# 612_jetracer_328_213.net
KiCad netlist of a schematic drawn in EAGLE
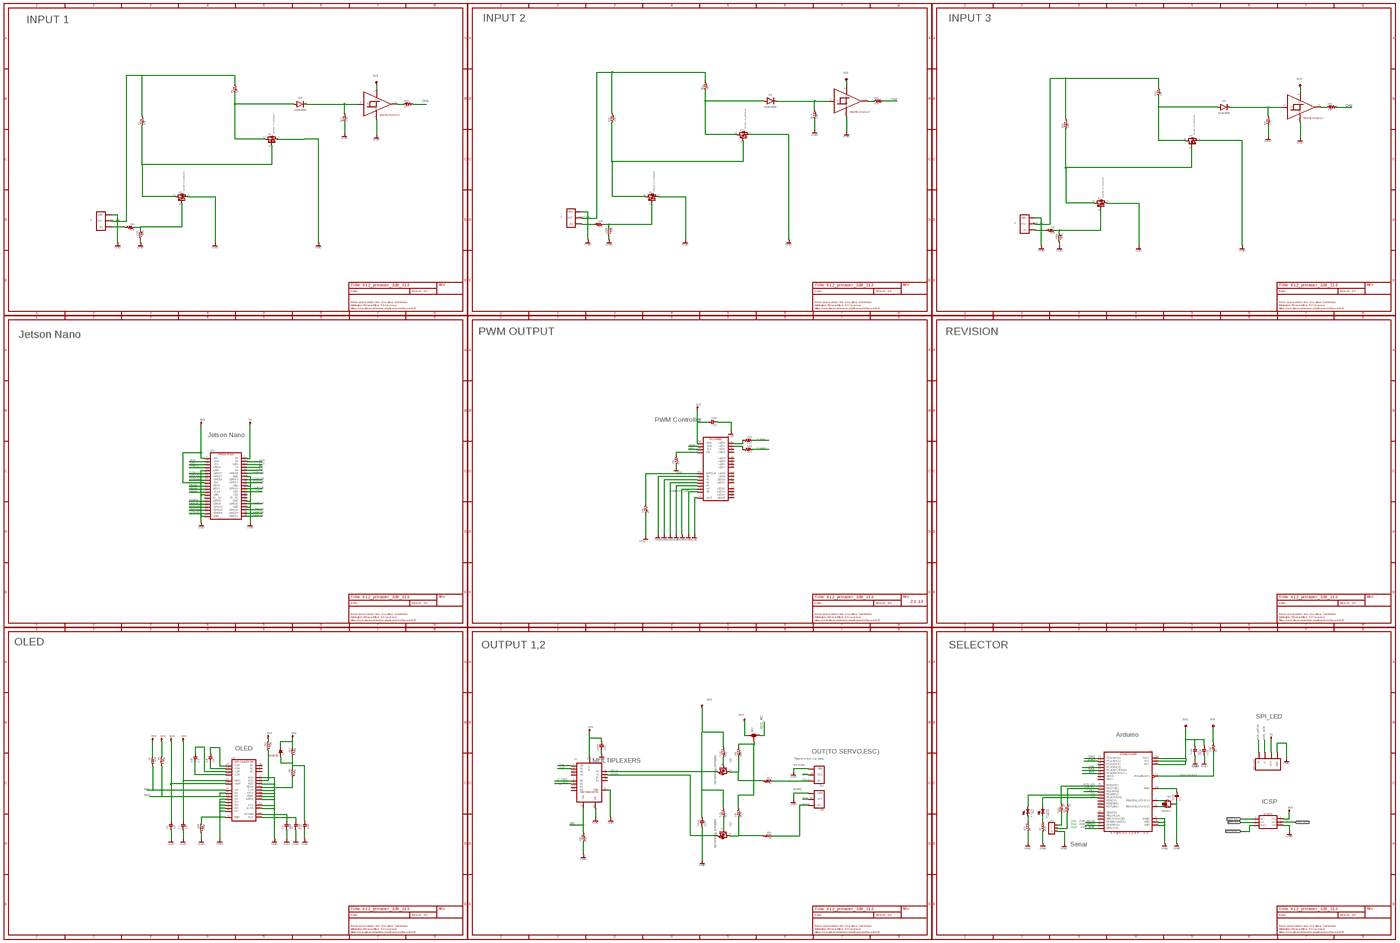
[diagram p0: schematic, sheet 1, overview]
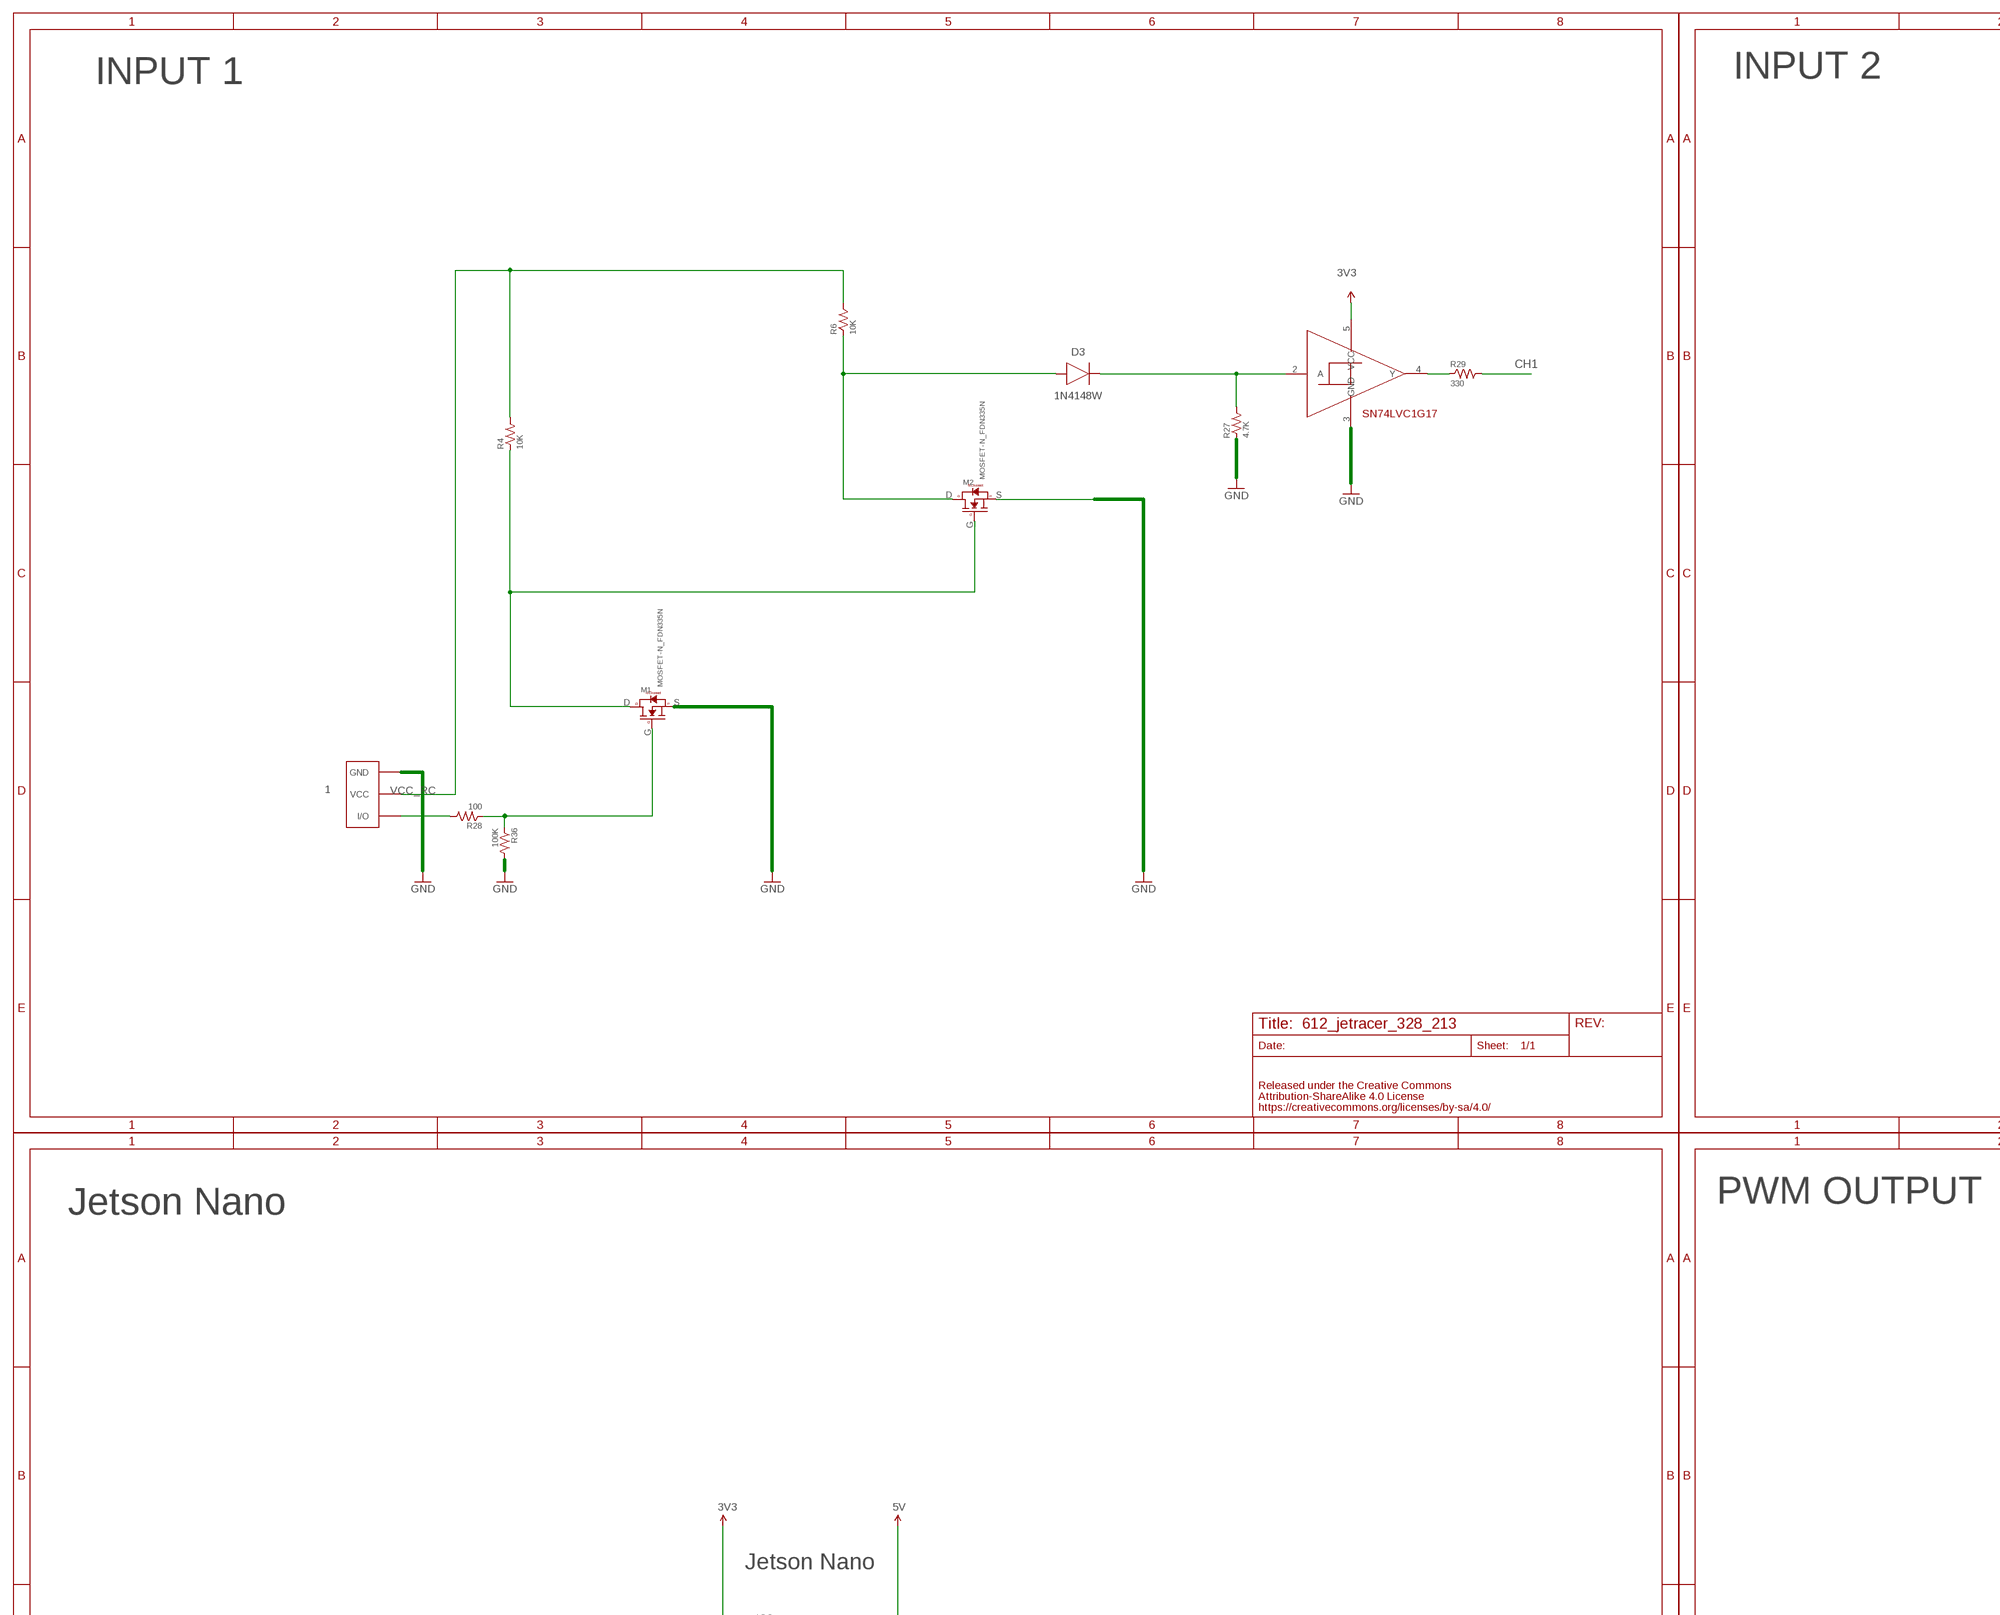
[diagram p1: schematic, sheet 1, part 1 of 6]
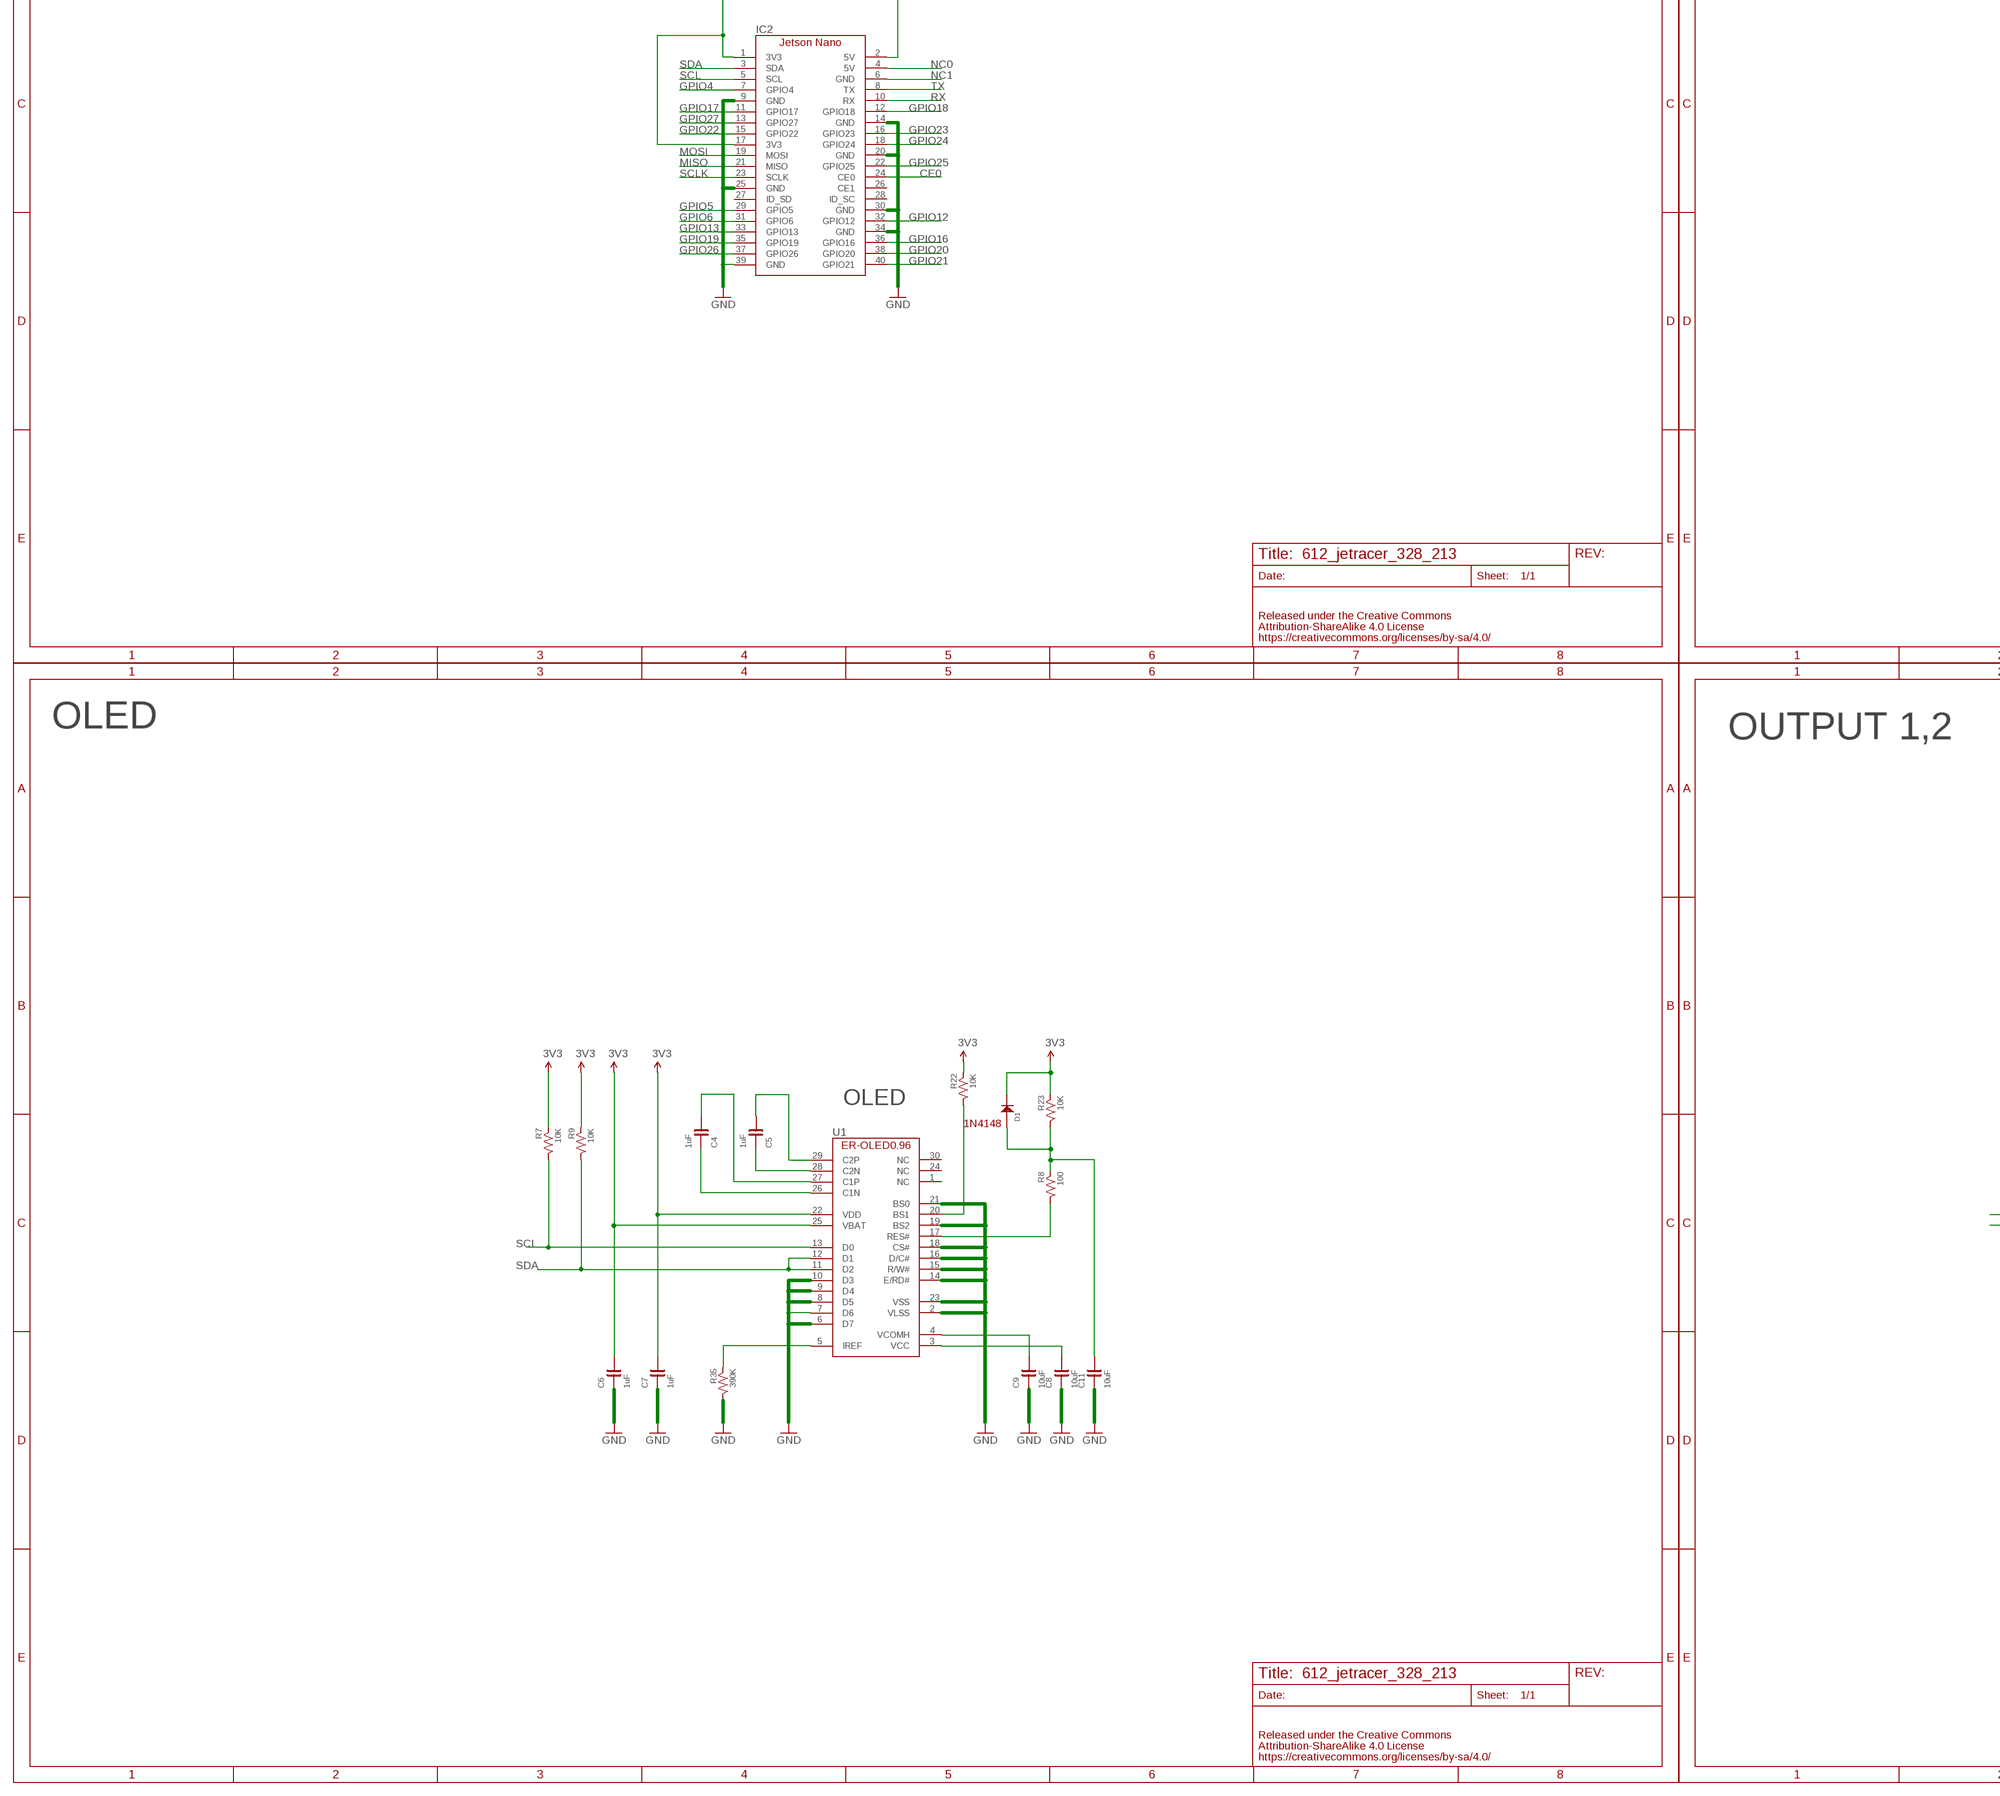
[diagram p2: schematic, sheet 1, part 2 of 6]
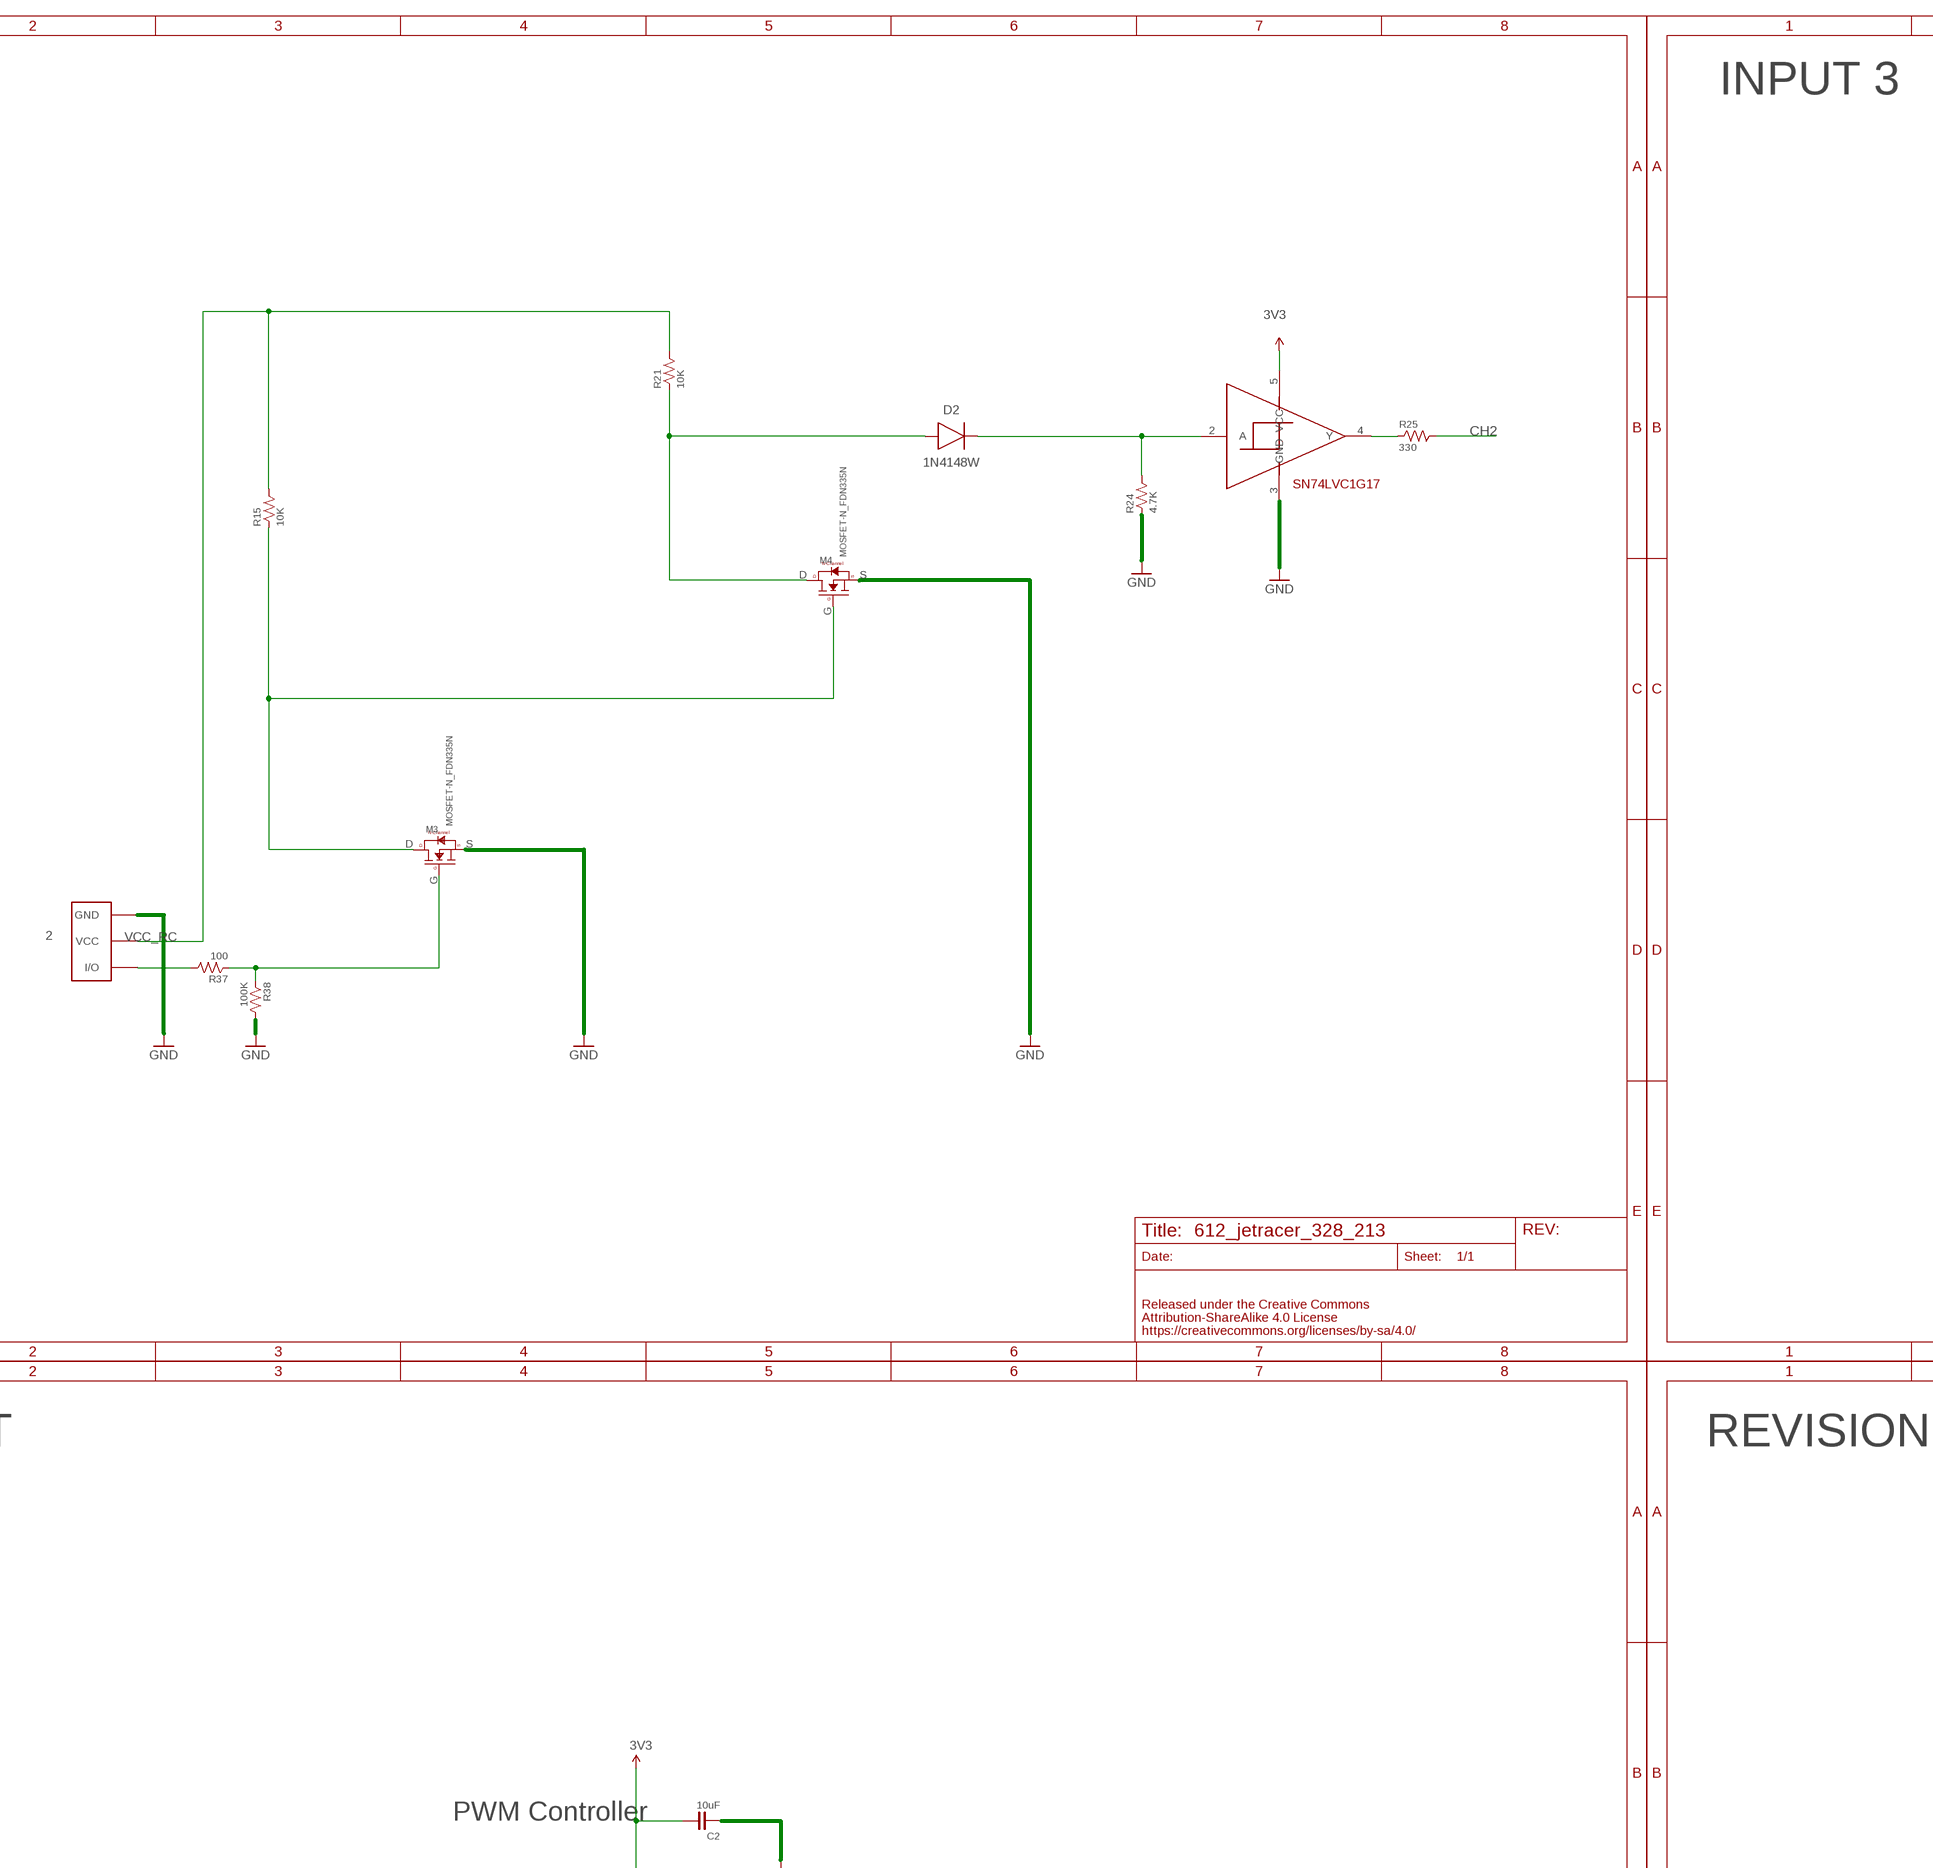
[diagram p3: schematic, sheet 1, part 3 of 6]
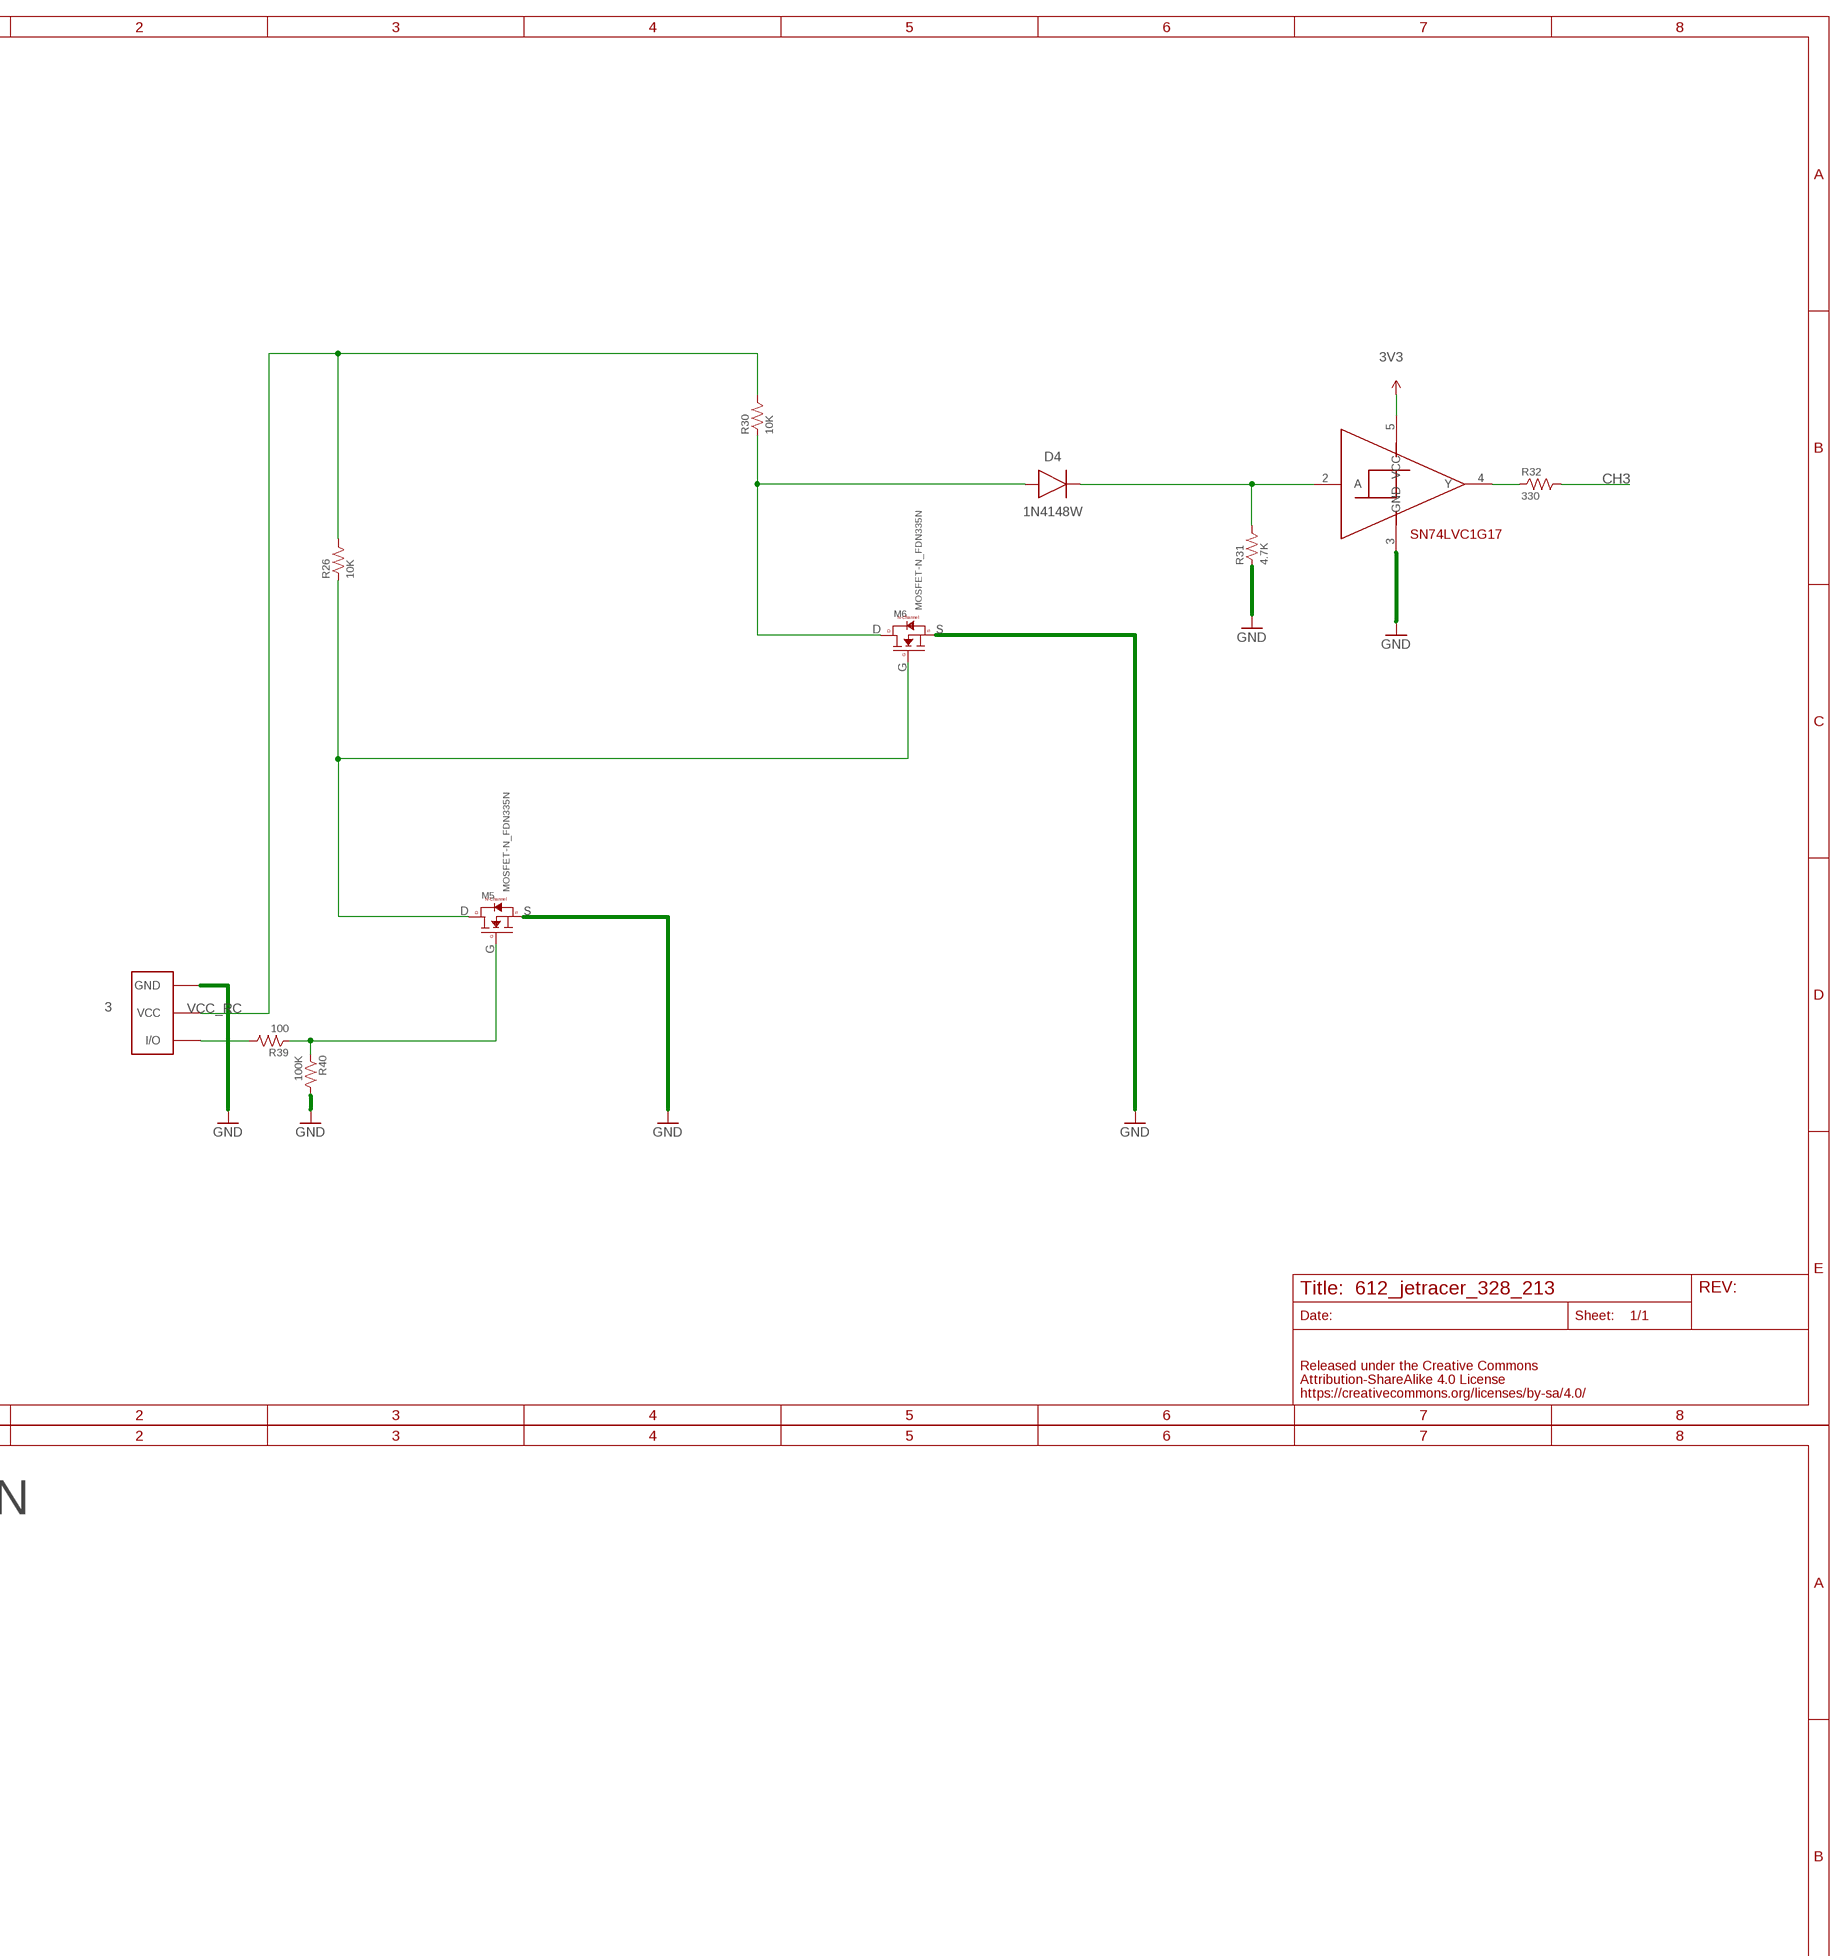
[diagram p4: schematic, sheet 1, part 4 of 6]
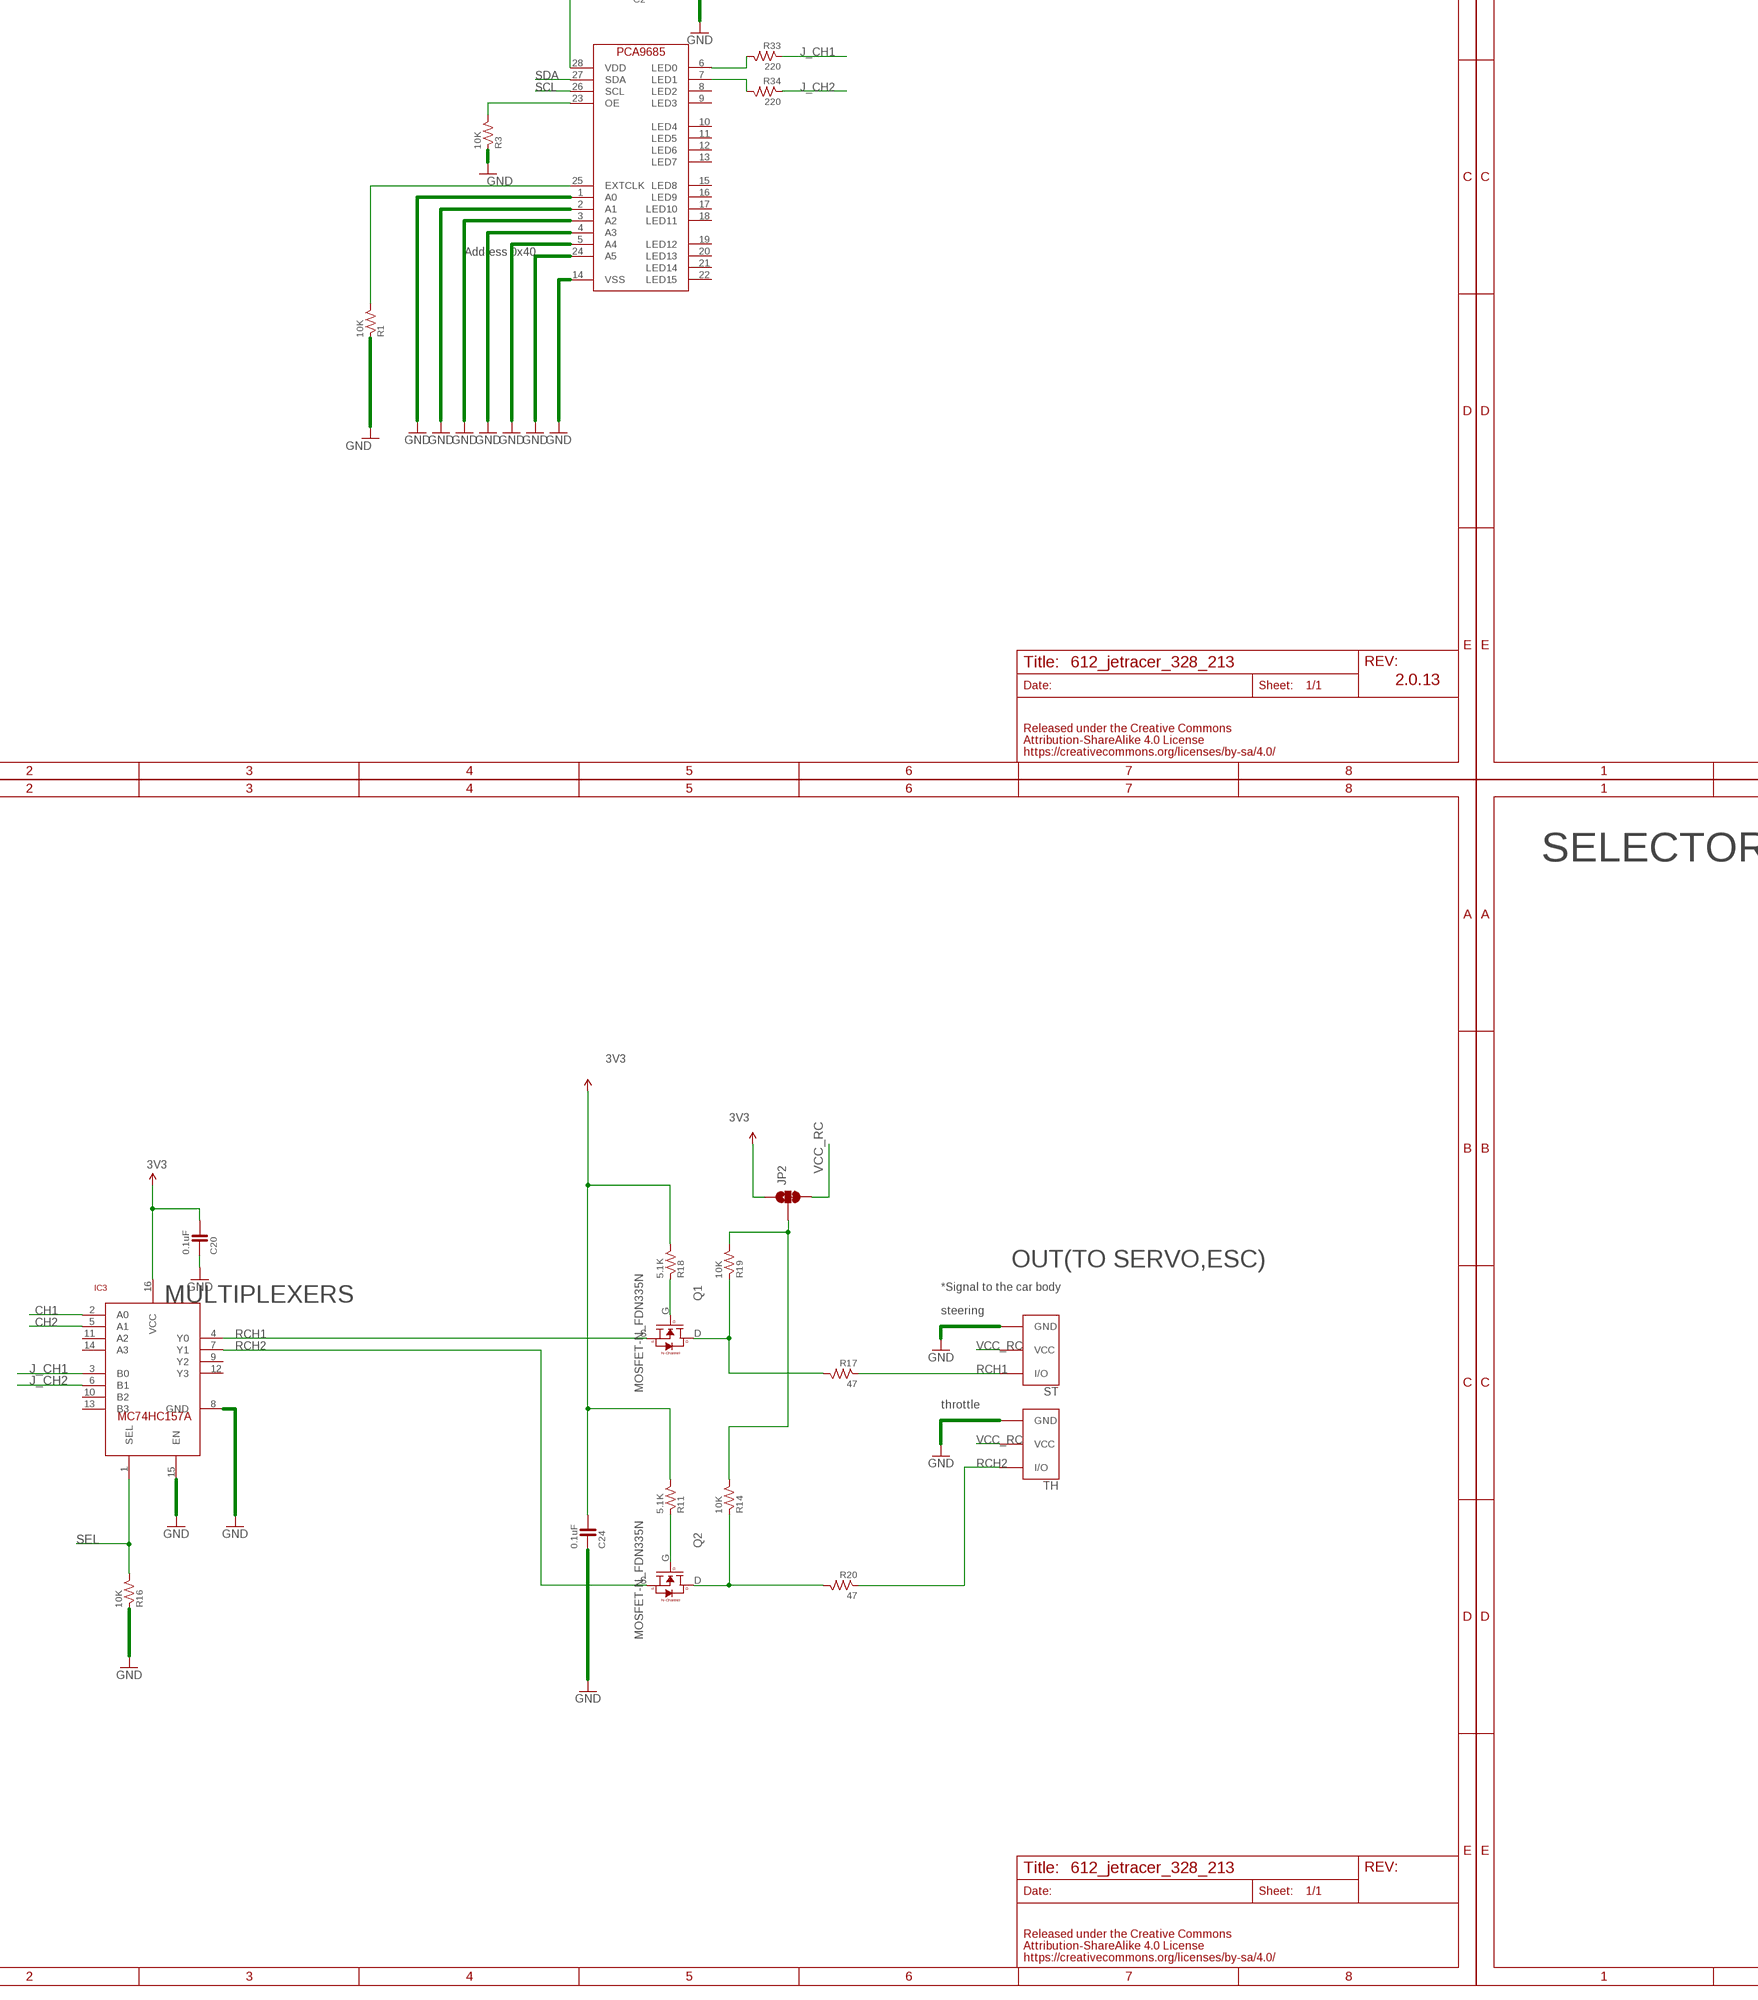
[diagram p5: schematic, sheet 1, part 5 of 6]
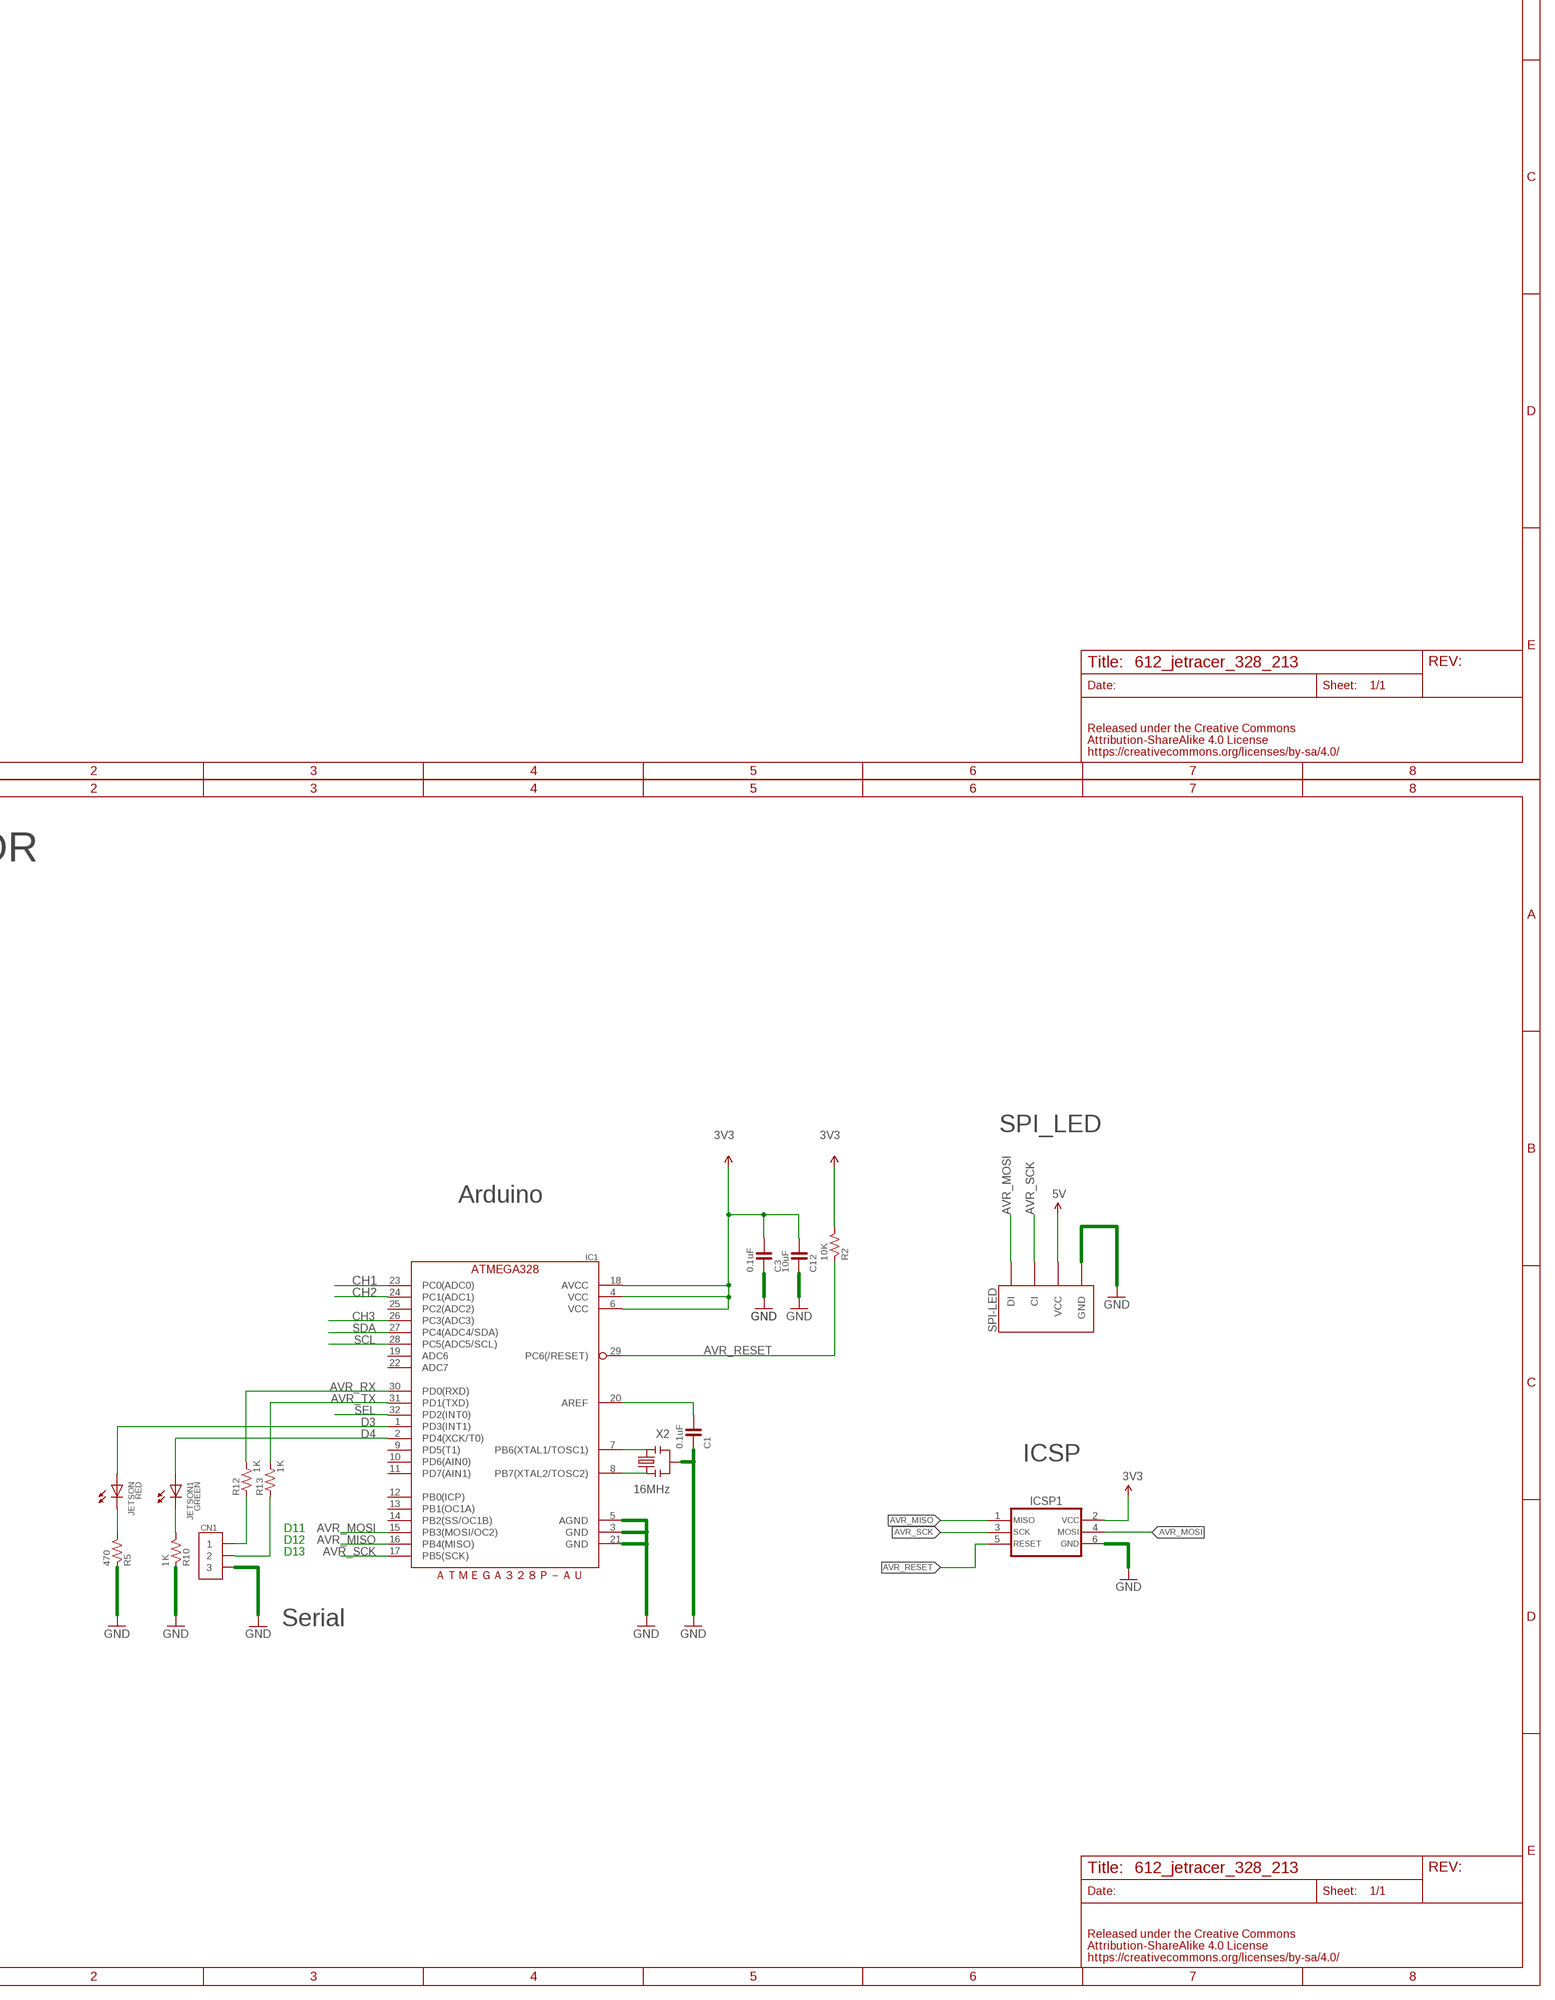
[diagram p6: schematic, sheet 1, part 6 of 6]

(export (version "E")
  (design (tool "Eeschema 10.0.6"))
  (components
    (comp (ref "1")
      (value "FABO_BRICK_3PIN-HEADER")
      (footprint "eagle-import:FABO_BRICK_3PIN_HEADER")
      (libsource (lib "eagle-import") (part "FABO_BRICK_3PIN-HEADER"))
    )
    (comp (ref "2")
      (value "FABO_BRICK_3PIN-HEADER")
      (footprint "eagle-import:FABO_BRICK_3PIN_HEADER")
      (libsource (lib "eagle-import") (part "FABO_BRICK_3PIN-HEADER"))
    )
    (comp (ref "3")
      (value "FABO_BRICK_3PIN-HEADER")
      (footprint "eagle-import:FABO_BRICK_3PIN_HEADER")
      (libsource (lib "eagle-import") (part "FABO_BRICK_3PIN-HEADER"))
    )
    (comp (ref "C1")
      (value "0.1uF")
      (footprint "eagle-import:0603")
      (libsource (lib "eagle-import") (part "CAPACITOR-0603"))
    )
    (comp (ref "C2")
      (value "10uF")
      (footprint "eagle-import:0603")
      (libsource (lib "eagle-import") (part "CAPACITOR-0603"))
    )
    (comp (ref "C3")
      (value "0.1uF")
      (footprint "eagle-import:0603")
      (libsource (lib "eagle-import") (part "CAPACITOR-0603"))
    )
    (comp (ref "C4")
      (value "1uF")
      (footprint "eagle-import:0603")
      (libsource (lib "eagle-import") (part "CAPACITOR-0603"))
    )
    (comp (ref "C5")
      (value "1uF")
      (footprint "eagle-import:0603")
      (libsource (lib "eagle-import") (part "CAPACITOR-0603"))
    )
    (comp (ref "C6")
      (value "1uF")
      (footprint "eagle-import:0603")
      (libsource (lib "eagle-import") (part "CAPACITOR-0603"))
    )
    (comp (ref "C7")
      (value "1uF")
      (footprint "eagle-import:0603")
      (libsource (lib "eagle-import") (part "CAPACITOR-0603"))
    )
    (comp (ref "C8")
      (value "10uF")
      (footprint "eagle-import:0603")
      (libsource (lib "eagle-import") (part "CAPACITOR-0603"))
    )
    (comp (ref "C9")
      (value "10uF")
      (footprint "eagle-import:0603")
      (libsource (lib "eagle-import") (part "CAPACITOR-0603"))
    )
    (comp (ref "C11")
      (value "10uF")
      (footprint "eagle-import:0603")
      (libsource (lib "eagle-import") (part "CAPACITOR-0603"))
    )
    (comp (ref "C12")
      (value "10uF")
      (footprint "eagle-import:0603")
      (libsource (lib "eagle-import") (part "CAPACITOR-0603"))
    )
    (comp (ref "C20")
      (value "0.1uF")
      (footprint "eagle-import:0603")
      (libsource (lib "eagle-import") (part "CAPACITOR-0603"))
    )
    (comp (ref "C24")
      (value "0.1uF")
      (footprint "eagle-import:0603")
      (fields (field (name "SPICEPREFIX") "C"))
      (libsource (lib "eagle-import") (part "CAPACITOR-0603"))
    )
    (comp (ref "CN1")
      (value "PIN_1X3")
      (footprint "eagle-import:PIN_1X3")
      (libsource (lib "eagle-import") (part "PIN_1X3"))
    )
    (comp (ref "D1")
      (value "1N4148")
      (footprint "eagle-import:1N4148W")
      (libsource (lib "eagle-import") (part "1N4148"))
    )
    (comp (ref "D2")
      (value "1N4148W")
      (footprint "eagle-import:SOD3715X135")
      (fields (field (name "MANUFACTURER") "Diodes Incorporated"))
      (libsource (lib "eagle-import") (part "DIODE__SOD123G1N4148W-7-F"))
    )
    (comp (ref "D3")
      (value "1N4148W")
      (footprint "eagle-import:SOD3715X135")
      (fields (field (name "MANUFACTURER") "Diodes Incorporated"))
      (libsource (lib "eagle-import") (part "DIODE__SOD123G1N4148W-7-F"))
    )
    (comp (ref "D4")
      (value "1N4148W")
      (footprint "eagle-import:SOD3715X135")
      (fields (field (name "MANUFACTURER") "Diodes Incorporated"))
      (libsource (lib "eagle-import") (part "DIODE__SOD123G1N4148W-7-F"))
    )
    (comp (ref "IC1")
      (value "ATMEGA328P-AU")
      (footprint "eagle-import:TQFP-32")
      (libsource (lib "eagle-import") (part "ATMEGA328P-AU"))
    )
    (comp (ref "IC2")
      (value "JETSON_NANO_NOBORDER")
      (footprint "eagle-import:JETSON_NANO_NOBOARDER")
      (libsource (lib "eagle-import") (part "JETSON_NANO_NOBORDER"))
    )
    (comp (ref "IC3")
      (value "MULTIPLEXERSMC74HC157A")
      (footprint "eagle-import:TSSOP-16")
      (libsource (lib "eagle-import") (part "MULTIPLEXERSMC74HC157A"))
    )
    (comp (ref "IC4")
      (value "PCA9685")
      (footprint "eagle-import:PCA9685")
      (libsource (lib "eagle-import") (part "PCA9685"))
    )
    (comp (ref "ICSP1")
      (value "ICSP_AVR-TC_NOHOLE")
      (footprint "eagle-import:TC2030")
      (libsource (lib "eagle-import") (part "ICSP_AVR-TC_NOHOLE"))
    )
    (comp (ref "JETSON")
      (value "GREEN")
      (footprint "eagle-import:0603")
      (libsource (lib "eagle-import") (part "LED-0603"))
    )
    (comp (ref "JETSON1")
      (value "RED")
      (footprint "eagle-import:0603")
      (libsource (lib "eagle-import") (part "LED-0603"))
    )
    (comp (ref "JP2")
      (value "JUMPER-SMT_3_1-NC_TRACE_SILK")
      (footprint "eagle-import:SMT-JUMPER_3_1-NC_TRACE_SILK")
      (libsource (lib "eagle-import") (part "JUMPER-SMT_3_1-NC_TRACE_SILK"))
    )
    (comp (ref "M1")
      (value "MOSFET-N_FDN335N")
      (footprint "eagle-import:SUPERSOT-3")
      (libsource (lib "eagle-import") (part "MOSFET-N_FDN335N"))
    )
    (comp (ref "M2")
      (value "MOSFET-N_FDN335N")
      (footprint "eagle-import:SUPERSOT-3")
      (libsource (lib "eagle-import") (part "MOSFET-N_FDN335N"))
    )
    (comp (ref "M3")
      (value "MOSFET-N_FDN335N")
      (footprint "eagle-import:SUPERSOT-3")
      (libsource (lib "eagle-import") (part "MOSFET-N_FDN335N"))
    )
    (comp (ref "M4")
      (value "MOSFET-N_FDN335N")
      (footprint "eagle-import:SUPERSOT-3")
      (libsource (lib "eagle-import") (part "MOSFET-N_FDN335N"))
    )
    (comp (ref "M5")
      (value "MOSFET-N_FDN335N")
      (footprint "eagle-import:SUPERSOT-3")
      (libsource (lib "eagle-import") (part "MOSFET-N_FDN335N"))
    )
    (comp (ref "M6")
      (value "MOSFET-N_FDN335N")
      (footprint "eagle-import:SUPERSOT-3")
      (libsource (lib "eagle-import") (part "MOSFET-N_FDN335N"))
    )
    (comp (ref "Q1")
      (value "MOSFET-N_FDN335N")
      (footprint "eagle-import:SUPERSOT-3")
      (libsource (lib "eagle-import") (part "MOSFET-N_FDN335N"))
    )
    (comp (ref "Q2")
      (value "MOSFET-N_FDN335N")
      (footprint "eagle-import:SUPERSOT-3")
      (libsource (lib "eagle-import") (part "MOSFET-N_FDN335N"))
    )
    (comp (ref "R1")
      (value "10K")
      (footprint "eagle-import:0603")
      (libsource (lib "eagle-import") (part "RESISTOR-0603"))
    )
    (comp (ref "R2")
      (value "10K")
      (footprint "eagle-import:0603")
      (libsource (lib "eagle-import") (part "RESISTOR-0603"))
    )
    (comp (ref "R3")
      (value "10K")
      (footprint "eagle-import:0603")
      (libsource (lib "eagle-import") (part "RESISTOR-0603"))
    )
    (comp (ref "R4")
      (value "10K")
      (footprint "eagle-import:0603")
      (libsource (lib "eagle-import") (part "RESISTOR-0603"))
    )
    (comp (ref "R5")
      (value "470")
      (footprint "eagle-import:0603")
      (libsource (lib "eagle-import") (part "RESISTOR-0603"))
    )
    (comp (ref "R6")
      (value "10K")
      (footprint "eagle-import:0603")
      (libsource (lib "eagle-import") (part "RESISTOR-0603"))
    )
    (comp (ref "R7")
      (value "10K")
      (footprint "eagle-import:0603")
      (libsource (lib "eagle-import") (part "RESISTOR-0603"))
    )
    (comp (ref "R8")
      (value "100")
      (footprint "eagle-import:0603")
      (libsource (lib "eagle-import") (part "RESISTOR-0603"))
    )
    (comp (ref "R9")
      (value "10K")
      (footprint "eagle-import:0603")
      (libsource (lib "eagle-import") (part "RESISTOR-0603"))
    )
    (comp (ref "R10")
      (value "1K")
      (footprint "eagle-import:0603")
      (libsource (lib "eagle-import") (part "RESISTOR-0603"))
    )
    (comp (ref "R11")
      (value "5.1K")
      (footprint "eagle-import:0603")
      (libsource (lib "eagle-import") (part "RESISTOR-0603"))
    )
    (comp (ref "R12")
      (value "1K")
      (footprint "eagle-import:0603")
      (libsource (lib "eagle-import") (part "RESISTOR-0603"))
    )
    (comp (ref "R13")
      (value "1K")
      (footprint "eagle-import:0603")
      (libsource (lib "eagle-import") (part "RESISTOR-0603"))
    )
    (comp (ref "R14")
      (value "10K")
      (footprint "eagle-import:0603")
      (libsource (lib "eagle-import") (part "RESISTOR-0603"))
    )
    (comp (ref "R15")
      (value "10K")
      (footprint "eagle-import:0603")
      (libsource (lib "eagle-import") (part "RESISTOR-0603"))
    )
    (comp (ref "R16")
      (value "10K")
      (footprint "eagle-import:0603")
      (libsource (lib "eagle-import") (part "RESISTOR-0603"))
    )
    (comp (ref "R17")
      (value "47")
      (footprint "eagle-import:0603")
      (libsource (lib "eagle-import") (part "RESISTOR-0603"))
    )
    (comp (ref "R18")
      (value "5.1K")
      (footprint "eagle-import:0603")
      (libsource (lib "eagle-import") (part "RESISTOR-0603"))
    )
    (comp (ref "R19")
      (value "10K")
      (footprint "eagle-import:0603")
      (libsource (lib "eagle-import") (part "RESISTOR-0603"))
    )
    (comp (ref "R20")
      (value "47")
      (footprint "eagle-import:0603")
      (libsource (lib "eagle-import") (part "RESISTOR-0603"))
    )
    (comp (ref "R21")
      (value "10K")
      (footprint "eagle-import:0603")
      (libsource (lib "eagle-import") (part "RESISTOR-0603"))
    )
    (comp (ref "R22")
      (value "10K")
      (footprint "eagle-import:0603")
      (libsource (lib "eagle-import") (part "RESISTOR-0603"))
    )
    (comp (ref "R23")
      (value "10K")
      (footprint "eagle-import:0603")
      (libsource (lib "eagle-import") (part "RESISTOR-0603"))
    )
    (comp (ref "R24")
      (value "4.7K")
      (footprint "eagle-import:0603")
      (libsource (lib "eagle-import") (part "RESISTOR-0603"))
    )
    (comp (ref "R25")
      (value "330")
      (footprint "eagle-import:0603")
      (libsource (lib "eagle-import") (part "RESISTOR-0603"))
    )
    (comp (ref "R26")
      (value "10K")
      (footprint "eagle-import:0603")
      (libsource (lib "eagle-import") (part "RESISTOR-0603"))
    )
    (comp (ref "R27")
      (value "4.7K")
      (footprint "eagle-import:0603")
      (libsource (lib "eagle-import") (part "RESISTOR-0603"))
    )
    (comp (ref "R28")
      (value "100")
      (footprint "eagle-import:0603")
      (libsource (lib "eagle-import") (part "RESISTOR-0603"))
    )
    (comp (ref "R29")
      (value "330")
      (footprint "eagle-import:0603")
      (libsource (lib "eagle-import") (part "RESISTOR-0603"))
    )
    (comp (ref "R30")
      (value "10K")
      (footprint "eagle-import:0603")
      (libsource (lib "eagle-import") (part "RESISTOR-0603"))
    )
    (comp (ref "R31")
      (value "4.7K")
      (footprint "eagle-import:0603")
      (libsource (lib "eagle-import") (part "RESISTOR-0603"))
    )
    (comp (ref "R32")
      (value "330")
      (footprint "eagle-import:0603")
      (libsource (lib "eagle-import") (part "RESISTOR-0603"))
    )
    (comp (ref "R33")
      (value "220")
      (footprint "eagle-import:0603")
      (libsource (lib "eagle-import") (part "RESISTOR-0603"))
    )
    (comp (ref "R34")
      (value "220")
      (footprint "eagle-import:0603")
      (libsource (lib "eagle-import") (part "RESISTOR-0603"))
    )
    (comp (ref "R35")
      (value "390K")
      (footprint "eagle-import:0603")
      (libsource (lib "eagle-import") (part "RESISTOR-0603"))
    )
    (comp (ref "R36")
      (value "100K")
      (footprint "eagle-import:0603")
      (libsource (lib "eagle-import") (part "RESISTOR-0603"))
    )
    (comp (ref "R37")
      (value "100")
      (footprint "eagle-import:0603")
      (libsource (lib "eagle-import") (part "RESISTOR-0603"))
    )
    (comp (ref "R38")
      (value "100K")
      (footprint "eagle-import:0603")
      (libsource (lib "eagle-import") (part "RESISTOR-0603"))
    )
    (comp (ref "R39")
      (value "100")
      (footprint "eagle-import:0603")
      (libsource (lib "eagle-import") (part "RESISTOR-0603"))
    )
    (comp (ref "R40")
      (value "100K")
      (footprint "eagle-import:0603")
      (libsource (lib "eagle-import") (part "RESISTOR-0603"))
    )
    (comp (ref "SPI-LED")
      (value "FABO-SPI-LED-B04B")
      (footprint "eagle-import:SPI-B04B-PASK-1")
      (libsource (lib "eagle-import") (part "FABO-SPI-LED-B04B"))
    )
    (comp (ref "ST")
      (value "FABO_BRICK_3PIN-HEADER")
      (footprint "eagle-import:FABO_BRICK_3PIN_HEADER")
      (libsource (lib "eagle-import") (part "FABO_BRICK_3PIN-HEADER"))
    )
    (comp (ref "TH")
      (value "FABO_BRICK_3PIN-HEADER")
      (footprint "eagle-import:FABO_BRICK_3PIN_HEADER")
      (libsource (lib "eagle-import") (part "FABO_BRICK_3PIN-HEADER"))
    )
    (comp (ref "U$14")
      (value "SN74LVC1G17")
      (footprint "eagle-import:SOT-23")
      (libsource (lib "eagle-import") (part "SN74LVC1G17"))
    )
    (comp (ref "U$20")
      (value "SN74LVC1G17")
      (footprint "eagle-import:SOT-23")
      (libsource (lib "eagle-import") (part "SN74LVC1G17"))
    )
    (comp (ref "U$23")
      (value "SN74LVC1G17")
      (footprint "eagle-import:SOT-23")
      (libsource (lib "eagle-import") (part "SN74LVC1G17"))
    )
    (comp (ref "U1")
      (value "ER-OLED0.96-1ER-CON30HT-1")
      (footprint "eagle-import:ER-CON30HT-1")
      (libsource (lib "eagle-import") (part "ER-OLED0.96-1ER-CON30HT-1"))
    )
    (comp (ref "X2")
      (value "16MHz")
      (footprint "eagle-import:CSTNE_V_C")
      (libsource (lib "eagle-import") (part "RESONATOR"))
    )
  )
  (nets
    (net (code "1") (name "/AVR_RX") (class "Default")
      (node (ref "IC1") (pin "30") (pinfunction "PD0(RXD)_30") (pintype "bidirectional"))
      (node (ref "R12") (pin "2") (pinfunction "2_2") (pintype "bidirectional"))
    )
    (net (code "2") (name "/AVR_TX") (class "Default")
      (node (ref "IC1") (pin "31") (pinfunction "PD1(TXD)_31") (pintype "bidirectional"))
      (node (ref "R13") (pin "2") (pinfunction "2_2") (pintype "bidirectional"))
    )
    (net (code "3") (name "/CE0") (class "Default")
      (node (ref "IC2") (pin "24") (pinfunction "CE0_24") (pintype "bidirectional"))
    )
    (net (code "4") (name "/CH1") (class "Default")
      (node (ref "IC1") (pin "23") (pinfunction "PC0(ADC0)_23") (pintype "bidirectional"))
      (node (ref "IC3") (pin "2") (pinfunction "A0_2") (pintype "bidirectional"))
      (node (ref "R29") (pin "2") (pinfunction "2_2") (pintype "bidirectional"))
    )
    (net (code "5") (name "/CH2") (class "Default")
      (node (ref "IC1") (pin "24") (pinfunction "PC1(ADC1)_24") (pintype "bidirectional"))
      (node (ref "IC3") (pin "5") (pinfunction "A1_5") (pintype "bidirectional"))
      (node (ref "R25") (pin "2") (pinfunction "2_2") (pintype "bidirectional"))
    )
    (net (code "6") (name "/CH3") (class "Default")
      (node (ref "IC1") (pin "26") (pinfunction "PC3(ADC3)_26") (pintype "bidirectional"))
      (node (ref "R32") (pin "2") (pinfunction "2_2") (pintype "bidirectional"))
    )
    (net (code "7") (name "/D3") (class "Default")
      (node (ref "IC1") (pin "1") (pinfunction "PD3(INT1)_1") (pintype "bidirectional"))
      (node (ref "JETSON1") (pin "ANODE") (pinfunction "ANODE_ANODE") (pintype "passive"))
    )
    (net (code "8") (name "/D4") (class "Default")
      (node (ref "IC1") (pin "2") (pinfunction "PD4(XCK/T0)_2") (pintype "bidirectional"))
      (node (ref "JETSON") (pin "ANODE") (pinfunction "ANODE_ANODE") (pintype "passive"))
    )
    (net (code "9") (name "/GPIO4") (class "Default")
      (node (ref "IC2") (pin "7") (pinfunction "GPIO4_7") (pintype "bidirectional"))
    )
    (net (code "10") (name "/GPIO5") (class "Default")
      (node (ref "IC2") (pin "29") (pinfunction "GPIO5_29") (pintype "bidirectional"))
    )
    (net (code "11") (name "/GPIO6") (class "Default")
      (node (ref "IC2") (pin "31") (pinfunction "GPIO6_31") (pintype "bidirectional"))
    )
    (net (code "12") (name "/GPIO12") (class "Default")
      (node (ref "IC2") (pin "32") (pinfunction "GPIO12_32") (pintype "bidirectional"))
    )
    (net (code "13") (name "/GPIO13") (class "Default")
      (node (ref "IC2") (pin "33") (pinfunction "GPIO13_33") (pintype "bidirectional"))
    )
    (net (code "14") (name "/GPIO16") (class "Default")
      (node (ref "IC2") (pin "36") (pinfunction "GPIO16_36") (pintype "bidirectional"))
    )
    (net (code "15") (name "/GPIO17") (class "Default")
      (node (ref "IC2") (pin "11") (pinfunction "GPIO17_11") (pintype "bidirectional"))
    )
    (net (code "16") (name "/GPIO18") (class "Default")
      (node (ref "IC2") (pin "12") (pinfunction "GPIO18_12") (pintype "bidirectional"))
    )
    (net (code "17") (name "/GPIO19") (class "Default")
      (node (ref "IC2") (pin "35") (pinfunction "GPIO19_35") (pintype "bidirectional"))
    )
    (net (code "18") (name "/GPIO20") (class "Default")
      (node (ref "IC2") (pin "38") (pinfunction "GPIO20_38") (pintype "bidirectional"))
    )
    (net (code "19") (name "/GPIO21") (class "Default")
      (node (ref "IC2") (pin "40") (pinfunction "GPIO21_40") (pintype "bidirectional"))
    )
    (net (code "20") (name "/GPIO22") (class "Default")
      (node (ref "IC2") (pin "15") (pinfunction "GPIO22_15") (pintype "bidirectional"))
    )
    (net (code "21") (name "/GPIO23") (class "Default")
      (node (ref "IC2") (pin "16") (pinfunction "GPIO23_16") (pintype "bidirectional"))
    )
    (net (code "22") (name "/GPIO24") (class "Default")
      (node (ref "IC2") (pin "18") (pinfunction "GPIO24_18") (pintype "bidirectional"))
    )
    (net (code "23") (name "/GPIO25") (class "Default")
      (node (ref "IC2") (pin "22") (pinfunction "GPIO25_22") (pintype "bidirectional"))
    )
    (net (code "24") (name "/GPIO26") (class "Default")
      (node (ref "IC2") (pin "37") (pinfunction "GPIO26_37") (pintype "bidirectional"))
    )
    (net (code "25") (name "/GPIO27") (class "Default")
      (node (ref "IC2") (pin "13") (pinfunction "GPIO27_13") (pintype "bidirectional"))
    )
    (net (code "26") (name "/J_CH1") (class "Default")
      (node (ref "IC3") (pin "3") (pinfunction "B0_3") (pintype "bidirectional"))
      (node (ref "R33") (pin "1") (pinfunction "1_1") (pintype "bidirectional"))
    )
    (net (code "27") (name "/J_CH2") (class "Default")
      (node (ref "IC3") (pin "6") (pinfunction "B1_6") (pintype "bidirectional"))
      (node (ref "R34") (pin "1") (pinfunction "1_1") (pintype "bidirectional"))
    )
    (net (code "28") (name "/MISO") (class "Default")
      (node (ref "IC2") (pin "21") (pinfunction "MISO_21") (pintype "bidirectional"))
    )
    (net (code "29") (name "/MOSI") (class "Default")
      (node (ref "IC2") (pin "19") (pinfunction "MOSI_19") (pintype "bidirectional"))
    )
    (net (code "30") (name "/NC0") (class "Default")
      (node (ref "IC2") (pin "4") (pinfunction "5V_4") (pintype "bidirectional"))
    )
    (net (code "31") (name "/NC1") (class "Default")
      (node (ref "IC2") (pin "6") (pinfunction "GND_6") (pintype "bidirectional"))
    )
    (net (code "32") (name "/RCH1") (class "Default")
      (node (ref "IC3") (pin "4") (pinfunction "Y0_4") (pintype "bidirectional"))
      (node (ref "Q1") (pin "S") (pinfunction "S_S") (pintype "passive"))
    )
    (net (code "33") (name "/RCH2") (class "Default")
      (node (ref "IC3") (pin "7") (pinfunction "Y1_7") (pintype "bidirectional"))
      (node (ref "Q2") (pin "S") (pinfunction "S_S") (pintype "passive"))
    )
    (net (code "34") (name "/RX") (class "Default")
      (node (ref "IC2") (pin "10") (pinfunction "RX_10") (pintype "bidirectional"))
    )
    (net (code "35") (name "/SCL") (class "Default")
      (node (ref "IC1") (pin "28") (pinfunction "PC5(ADC5/SCL)_28") (pintype "bidirectional"))
      (node (ref "IC2") (pin "5") (pinfunction "SCL_5") (pintype "bidirectional"))
      (node (ref "IC4") (pin "26") (pinfunction "SCL_26") (pintype "bidirectional"))
      (node (ref "R7") (pin "2") (pinfunction "2_2") (pintype "bidirectional"))
      (node (ref "U1") (pin "13") (pinfunction "D0_13") (pintype "bidirectional"))
    )
    (net (code "36") (name "/SCLK") (class "Default")
      (node (ref "IC2") (pin "23") (pinfunction "SCLK_23") (pintype "bidirectional"))
    )
    (net (code "37") (name "/SDA") (class "Default")
      (node (ref "IC1") (pin "27") (pinfunction "PC4(ADC4/SDA)_27") (pintype "bidirectional"))
      (node (ref "IC2") (pin "3") (pinfunction "SDA_3") (pintype "bidirectional"))
      (node (ref "IC4") (pin "27") (pinfunction "SDA_27") (pintype "bidirectional"))
      (node (ref "R9") (pin "2") (pinfunction "2_2") (pintype "bidirectional"))
      (node (ref "U1") (pin "11") (pinfunction "D2_11") (pintype "bidirectional"))
      (node (ref "U1") (pin "12") (pinfunction "D1_12") (pintype "bidirectional"))
    )
    (net (code "38") (name "/SEL") (class "Default")
      (node (ref "IC1") (pin "32") (pinfunction "PD2(INT0)_32") (pintype "bidirectional"))
      (node (ref "IC3") (pin "1") (pinfunction "SEL_1") (pintype "bidirectional"))
      (node (ref "R16") (pin "2") (pinfunction "2_2") (pintype "bidirectional"))
    )
    (net (code "39") (name "/TX") (class "Default")
      (node (ref "IC2") (pin "8") (pinfunction "TX_8") (pintype "bidirectional"))
    )
    (net (code "40") (name "/VCC_RC") (class "Default")
      (node (ref "1") (pin "VCC") (pinfunction "VCC_VCC") (pintype "bidirectional"))
      (node (ref "2") (pin "VCC") (pinfunction "VCC_VCC") (pintype "bidirectional"))
      (node (ref "3") (pin "VCC") (pinfunction "VCC_VCC") (pintype "bidirectional"))
      (node (ref "JP2") (pin "3") (pinfunction "3_3") (pintype "passive"))
      (node (ref "R15") (pin "2") (pinfunction "2_2") (pintype "bidirectional"))
      (node (ref "R21") (pin "2") (pinfunction "2_2") (pintype "bidirectional"))
      (node (ref "R26") (pin "2") (pinfunction "2_2") (pintype "bidirectional"))
      (node (ref "R30") (pin "2") (pinfunction "2_2") (pintype "bidirectional"))
      (node (ref "R4") (pin "2") (pinfunction "2_2") (pintype "bidirectional"))
      (node (ref "R6") (pin "2") (pinfunction "2_2") (pintype "bidirectional"))
      (node (ref "ST") (pin "VCC") (pinfunction "VCC_VCC") (pintype "bidirectional"))
      (node (ref "TH") (pin "VCC") (pinfunction "VCC_VCC") (pintype "bidirectional"))
    )
    (net (code "41") (name "3V3") (class "Default")
      (node (ref "C12") (pin "2") (pinfunction "2_2") (pintype "passive"))
      (node (ref "C2") (pin "2") (pinfunction "2_2") (pintype "passive"))
      (node (ref "C20") (pin "2") (pinfunction "2_2") (pintype "passive"))
      (node (ref "C24") (pin "2") (pinfunction "2_2") (pintype "passive"))
      (node (ref "C3") (pin "2") (pinfunction "2_2") (pintype "passive"))
      (node (ref "C6") (pin "2") (pinfunction "2_2") (pintype "passive"))
      (node (ref "C7") (pin "2") (pinfunction "2_2") (pintype "passive"))
      (node (ref "D1") (pin "CATHODE") (pinfunction "CATHODE_CATHODE") (pintype "bidirectional"))
      (node (ref "IC1") (pin "18") (pinfunction "AVCC_18") (pintype "bidirectional"))
      (node (ref "IC1") (pin "4") (pinfunction "VCC_4") (pintype "bidirectional"))
      (node (ref "IC1") (pin "6") (pinfunction "VCC_6") (pintype "bidirectional"))
      (node (ref "IC2") (pin "1") (pinfunction "3V3_1") (pintype "bidirectional"))
      (node (ref "IC2") (pin "17") (pinfunction "3V3_17") (pintype "bidirectional"))
      (node (ref "IC3") (pin "16") (pinfunction "VCC_16") (pintype "bidirectional"))
      (node (ref "IC4") (pin "28") (pinfunction "VDD_28") (pintype "bidirectional"))
      (node (ref "ICSP1") (pin "2") (pinfunction "2_2") (pintype "passive"))
      (node (ref "JP2") (pin "1") (pinfunction "1_1") (pintype "passive"))
      (node (ref "R11") (pin "2") (pinfunction "2_2") (pintype "bidirectional"))
      (node (ref "R18") (pin "2") (pinfunction "2_2") (pintype "bidirectional"))
      (node (ref "R2") (pin "2") (pinfunction "2_2") (pintype "bidirectional"))
      (node (ref "R22") (pin "1") (pinfunction "1_1") (pintype "bidirectional"))
      (node (ref "R23") (pin "1") (pinfunction "1_1") (pintype "bidirectional"))
      (node (ref "R7") (pin "1") (pinfunction "1_1") (pintype "bidirectional"))
      (node (ref "R9") (pin "1") (pinfunction "1_1") (pintype "bidirectional"))
      (node (ref "U$14") (pin "5") (pinfunction "VCC_5") (pintype "bidirectional"))
      (node (ref "U$20") (pin "5") (pinfunction "VCC_5") (pintype "bidirectional"))
      (node (ref "U$23") (pin "5") (pinfunction "VCC_5") (pintype "bidirectional"))
      (node (ref "U1") (pin "22") (pinfunction "VDD_22") (pintype "bidirectional"))
      (node (ref "U1") (pin "25") (pinfunction "VBAT_25") (pintype "bidirectional"))
    )
    (net (code "42") (name "5V") (class "Default")
      (node (ref "IC2") (pin "2") (pinfunction "5V_2") (pintype "bidirectional"))
      (node (ref "SPI-LED") (pin "VCC") (pinfunction "VCC_VCC") (pintype "bidirectional"))
    )
    (net (code "43") (name "AVR_MISO") (class "Default")
      (node (ref "IC1") (pin "16") (pinfunction "PB4(MISO)_16") (pintype "bidirectional"))
      (node (ref "ICSP1") (pin "1") (pinfunction "1_1") (pintype "passive"))
    )
    (net (code "44") (name "AVR_MOSI") (class "Default")
      (node (ref "IC1") (pin "15") (pinfunction "PB3(MOSI/OC2)_15") (pintype "bidirectional"))
      (node (ref "ICSP1") (pin "4") (pinfunction "4_4") (pintype "passive"))
      (node (ref "SPI-LED") (pin "DI") (pinfunction "DI_DI") (pintype "bidirectional"))
    )
    (net (code "45") (name "AVR_RESET") (class "Default")
      (node (ref "IC1") (pin "29") (pinfunction "PC6(/RESET)_29") (pintype "bidirectional"))
      (node (ref "ICSP1") (pin "5") (pinfunction "5_5") (pintype "passive"))
      (node (ref "R2") (pin "1") (pinfunction "1_1") (pintype "bidirectional"))
    )
    (net (code "46") (name "AVR_SCK") (class "Default")
      (node (ref "IC1") (pin "17") (pinfunction "PB5(SCK)_17") (pintype "bidirectional"))
      (node (ref "ICSP1") (pin "3") (pinfunction "3_3") (pintype "passive"))
      (node (ref "SPI-LED") (pin "CI") (pinfunction "CI_CI") (pintype "bidirectional"))
    )
    (net (code "47") (name "GND") (class "Default")
      (node (ref "1") (pin "GND") (pinfunction "GND_GND") (pintype "bidirectional"))
      (node (ref "2") (pin "GND") (pinfunction "GND_GND") (pintype "bidirectional"))
      (node (ref "3") (pin "GND") (pinfunction "GND_GND") (pintype "bidirectional"))
      (node (ref "C1") (pin "1") (pinfunction "1_1") (pintype "passive"))
      (node (ref "C11") (pin "1") (pinfunction "1_1") (pintype "passive"))
      (node (ref "C12") (pin "1") (pinfunction "1_1") (pintype "passive"))
      (node (ref "C2") (pin "1") (pinfunction "1_1") (pintype "passive"))
      (node (ref "C20") (pin "1") (pinfunction "1_1") (pintype "passive"))
      (node (ref "C24") (pin "1") (pinfunction "1_1") (pintype "passive"))
      (node (ref "C3") (pin "1") (pinfunction "1_1") (pintype "passive"))
      (node (ref "C6") (pin "1") (pinfunction "1_1") (pintype "passive"))
      (node (ref "C7") (pin "1") (pinfunction "1_1") (pintype "passive"))
      (node (ref "C8") (pin "1") (pinfunction "1_1") (pintype "passive"))
      (node (ref "C9") (pin "1") (pinfunction "1_1") (pintype "passive"))
      (node (ref "CN1") (pin "3") (pinfunction "3_3") (pintype "bidirectional"))
      (node (ref "IC1") (pin "21") (pinfunction "GND_21") (pintype "bidirectional"))
      (node (ref "IC1") (pin "3") (pinfunction "GND_3") (pintype "bidirectional"))
      (node (ref "IC1") (pin "5") (pinfunction "AGND_5") (pintype "bidirectional"))
      (node (ref "IC2") (pin "14") (pinfunction "GND_14") (pintype "bidirectional"))
      (node (ref "IC2") (pin "20") (pinfunction "GND_20") (pintype "bidirectional"))
      (node (ref "IC2") (pin "25") (pinfunction "GND_25") (pintype "bidirectional"))
      (node (ref "IC2") (pin "30") (pinfunction "GND_30") (pintype "bidirectional"))
      (node (ref "IC2") (pin "34") (pinfunction "GND_34") (pintype "bidirectional"))
      (node (ref "IC2") (pin "39") (pinfunction "GND_39") (pintype "bidirectional"))
      (node (ref "IC2") (pin "9") (pinfunction "GND_9") (pintype "bidirectional"))
      (node (ref "IC3") (pin "15") (pinfunction "EN_15") (pintype "bidirectional"))
      (node (ref "IC3") (pin "8") (pinfunction "GND_8") (pintype "bidirectional"))
      (node (ref "IC4") (pin "1") (pinfunction "A0_1") (pintype "bidirectional"))
      (node (ref "IC4") (pin "14") (pinfunction "VSS_14") (pintype "bidirectional"))
      (node (ref "IC4") (pin "2") (pinfunction "A1_2") (pintype "bidirectional"))
      (node (ref "IC4") (pin "24") (pinfunction "A5_24") (pintype "bidirectional"))
      (node (ref "IC4") (pin "3") (pinfunction "A2_3") (pintype "bidirectional"))
      (node (ref "IC4") (pin "4") (pinfunction "A3_4") (pintype "bidirectional"))
      (node (ref "IC4") (pin "5") (pinfunction "A4_5") (pintype "bidirectional"))
      (node (ref "ICSP1") (pin "6") (pinfunction "6_6") (pintype "passive"))
      (node (ref "M1") (pin "S") (pinfunction "S_S") (pintype "passive"))
      (node (ref "M2") (pin "S") (pinfunction "S_S") (pintype "passive"))
      (node (ref "M3") (pin "S") (pinfunction "S_S") (pintype "passive"))
      (node (ref "M4") (pin "S") (pinfunction "S_S") (pintype "passive"))
      (node (ref "M5") (pin "S") (pinfunction "S_S") (pintype "passive"))
      (node (ref "M6") (pin "S") (pinfunction "S_S") (pintype "passive"))
      (node (ref "R1") (pin "1") (pinfunction "1_1") (pintype "bidirectional"))
      (node (ref "R10") (pin "1") (pinfunction "1_1") (pintype "bidirectional"))
      (node (ref "R16") (pin "1") (pinfunction "1_1") (pintype "bidirectional"))
      (node (ref "R24") (pin "1") (pinfunction "1_1") (pintype "bidirectional"))
      (node (ref "R27") (pin "1") (pinfunction "1_1") (pintype "bidirectional"))
      (node (ref "R3") (pin "1") (pinfunction "1_1") (pintype "bidirectional"))
      (node (ref "R31") (pin "1") (pinfunction "1_1") (pintype "bidirectional"))
      (node (ref "R35") (pin "2") (pinfunction "2_2") (pintype "bidirectional"))
      (node (ref "R36") (pin "2") (pinfunction "2_2") (pintype "bidirectional"))
      (node (ref "R38") (pin "2") (pinfunction "2_2") (pintype "bidirectional"))
      (node (ref "R40") (pin "2") (pinfunction "2_2") (pintype "bidirectional"))
      (node (ref "R5") (pin "1") (pinfunction "1_1") (pintype "bidirectional"))
      (node (ref "SPI-LED") (pin "GND") (pinfunction "GND_GND") (pintype "bidirectional"))
      (node (ref "ST") (pin "GND") (pinfunction "GND_GND") (pintype "bidirectional"))
      (node (ref "TH") (pin "GND") (pinfunction "GND_GND") (pintype "bidirectional"))
      (node (ref "U$14") (pin "3") (pinfunction "GND_3") (pintype "bidirectional"))
      (node (ref "U$20") (pin "3") (pinfunction "GND_3") (pintype "bidirectional"))
      (node (ref "U$23") (pin "3") (pinfunction "GND_3") (pintype "bidirectional"))
      (node (ref "U1") (pin "10") (pinfunction "D3_10") (pintype "bidirectional"))
      (node (ref "U1") (pin "14") (pinfunction "E/RD#_14") (pintype "bidirectional"))
      (node (ref "U1") (pin "15") (pinfunction "R/W#_15") (pintype "bidirectional"))
      (node (ref "U1") (pin "16") (pinfunction "D/C#_16") (pintype "bidirectional"))
      (node (ref "U1") (pin "18") (pinfunction "CS#_18") (pintype "bidirectional"))
      (node (ref "U1") (pin "19") (pinfunction "BS2_19") (pintype "bidirectional"))
      (node (ref "U1") (pin "2") (pinfunction "VLSS_2") (pintype "bidirectional"))
      (node (ref "U1") (pin "21") (pinfunction "BS0_21") (pintype "bidirectional"))
      (node (ref "U1") (pin "23") (pinfunction "VSS_23") (pintype "bidirectional"))
      (node (ref "U1") (pin "6") (pinfunction "D7_6") (pintype "bidirectional"))
      (node (ref "U1") (pin "7") (pinfunction "D6_7") (pintype "bidirectional"))
      (node (ref "U1") (pin "8") (pinfunction "D5_8") (pintype "bidirectional"))
      (node (ref "U1") (pin "9") (pinfunction "D4_9") (pintype "bidirectional"))
      (node (ref "X2") (pin "2") (pinfunction "2_2") (pintype "passive"))
    )
    (net (code "48") (name "Net-(1-PadI{slash}O)") (class "Default")
      (node (ref "1") (pin "I/O") (pinfunction "I/O_I/O") (pintype "bidirectional"))
      (node (ref "R28") (pin "2") (pinfunction "2_2") (pintype "bidirectional"))
    )
    (net (code "49") (name "Net-(2-PadI{slash}O)") (class "Default")
      (node (ref "2") (pin "I/O") (pinfunction "I/O_I/O") (pintype "bidirectional"))
      (node (ref "R37") (pin "2") (pinfunction "2_2") (pintype "bidirectional"))
    )
    (net (code "50") (name "Net-(3-PadI{slash}O)") (class "Default")
      (node (ref "3") (pin "I/O") (pinfunction "I/O_I/O") (pintype "bidirectional"))
      (node (ref "R39") (pin "2") (pinfunction "2_2") (pintype "bidirectional"))
    )
    (net (code "51") (name "Net-(C11-Pad2)") (class "Default")
      (node (ref "C11") (pin "2") (pinfunction "2_2") (pintype "passive"))
      (node (ref "D1") (pin "ANODE") (pinfunction "ANODE_ANODE") (pintype "bidirectional"))
      (node (ref "R23") (pin "2") (pinfunction "2_2") (pintype "bidirectional"))
      (node (ref "R8") (pin "1") (pinfunction "1_1") (pintype "bidirectional"))
    )
    (net (code "52") (name "Net-(CN1-Pad1)") (class "Default")
      (node (ref "CN1") (pin "1") (pinfunction "1_1") (pintype "bidirectional"))
      (node (ref "R12") (pin "1") (pinfunction "1_1") (pintype "bidirectional"))
    )
    (net (code "53") (name "Net-(CN1-Pad2)") (class "Default")
      (node (ref "CN1") (pin "2") (pinfunction "2_2") (pintype "bidirectional"))
      (node (ref "R13") (pin "1") (pinfunction "1_1") (pintype "bidirectional"))
    )
    (net (code "54") (name "Net-(D2-A)") (class "Default")
      (node (ref "D2") (pin "2") (pinfunction "A_2") (pintype "passive"))
      (node (ref "M4") (pin "D") (pinfunction "D_D") (pintype "passive"))
      (node (ref "R21") (pin "1") (pinfunction "1_1") (pintype "bidirectional"))
    )
    (net (code "55") (name "Net-(D2-C)") (class "Default")
      (node (ref "D2") (pin "1") (pinfunction "C_1") (pintype "passive"))
      (node (ref "R24") (pin "2") (pinfunction "2_2") (pintype "bidirectional"))
      (node (ref "U$20") (pin "2") (pinfunction "A_2") (pintype "bidirectional"))
    )
    (net (code "56") (name "Net-(D3-A)") (class "Default")
      (node (ref "D3") (pin "2") (pinfunction "A_2") (pintype "passive"))
      (node (ref "M2") (pin "D") (pinfunction "D_D") (pintype "passive"))
      (node (ref "R6") (pin "1") (pinfunction "1_1") (pintype "bidirectional"))
    )
    (net (code "57") (name "Net-(D3-C)") (class "Default")
      (node (ref "D3") (pin "1") (pinfunction "C_1") (pintype "passive"))
      (node (ref "R27") (pin "2") (pinfunction "2_2") (pintype "bidirectional"))
      (node (ref "U$14") (pin "2") (pinfunction "A_2") (pintype "bidirectional"))
    )
    (net (code "58") (name "Net-(D4-A)") (class "Default")
      (node (ref "D4") (pin "2") (pinfunction "A_2") (pintype "passive"))
      (node (ref "M6") (pin "D") (pinfunction "D_D") (pintype "passive"))
      (node (ref "R30") (pin "1") (pinfunction "1_1") (pintype "bidirectional"))
    )
    (net (code "59") (name "Net-(D4-C)") (class "Default")
      (node (ref "D4") (pin "1") (pinfunction "C_1") (pintype "passive"))
      (node (ref "R31") (pin "2") (pinfunction "2_2") (pintype "bidirectional"))
      (node (ref "U$23") (pin "2") (pinfunction "A_2") (pintype "bidirectional"))
    )
    (net (code "60") (name "Net-(IC1-AREF)") (class "Default")
      (node (ref "C1") (pin "2") (pinfunction "2_2") (pintype "passive"))
      (node (ref "IC1") (pin "20") (pinfunction "AREF_20") (pintype "bidirectional"))
    )
    (net (code "61") (name "Net-(IC1-PB6(XTAL1{slash}TOSC1))") (class "Default")
      (node (ref "IC1") (pin "7") (pinfunction "PB6(XTAL1/TOSC1)_7") (pintype "bidirectional"))
      (node (ref "X2") (pin "1") (pinfunction "1_1") (pintype "passive"))
    )
    (net (code "62") (name "Net-(IC1-PB7(XTAL2{slash}TOSC2))") (class "Default")
      (node (ref "IC1") (pin "8") (pinfunction "PB7(XTAL2/TOSC2)_8") (pintype "bidirectional"))
      (node (ref "X2") (pin "3") (pinfunction "3_3") (pintype "passive"))
    )
    (net (code "63") (name "Net-(IC4-EXTCLK)") (class "Default")
      (node (ref "IC4") (pin "25") (pinfunction "EXTCLK_25") (pintype "bidirectional"))
      (node (ref "R1") (pin "2") (pinfunction "2_2") (pintype "bidirectional"))
    )
    (net (code "64") (name "Net-(IC4-LED0)") (class "Default")
      (node (ref "IC4") (pin "6") (pinfunction "LED0_6") (pintype "bidirectional"))
      (node (ref "R33") (pin "2") (pinfunction "2_2") (pintype "bidirectional"))
    )
    (net (code "65") (name "Net-(IC4-LED1)") (class "Default")
      (node (ref "IC4") (pin "7") (pinfunction "LED1_7") (pintype "bidirectional"))
      (node (ref "R34") (pin "2") (pinfunction "2_2") (pintype "bidirectional"))
    )
    (net (code "66") (name "Net-(IC4-OE)") (class "Default")
      (node (ref "IC4") (pin "23") (pinfunction "OE_23") (pintype "bidirectional"))
      (node (ref "R3") (pin "2") (pinfunction "2_2") (pintype "bidirectional"))
    )
    (net (code "67") (name "Net-(JETSON-PadCATHODE)") (class "Default")
      (node (ref "JETSON") (pin "CATHODE") (pinfunction "CATHODE_CATHODE") (pintype "passive"))
      (node (ref "R10") (pin "2") (pinfunction "2_2") (pintype "bidirectional"))
    )
    (net (code "68") (name "Net-(JETSON1-PadCATHODE)") (class "Default")
      (node (ref "JETSON1") (pin "CATHODE") (pinfunction "CATHODE_CATHODE") (pintype "passive"))
      (node (ref "R5") (pin "2") (pinfunction "2_2") (pintype "bidirectional"))
    )
    (net (code "69") (name "Net-(JP2-Pad2)") (class "Default")
      (node (ref "JP2") (pin "2") (pinfunction "2_2") (pintype "passive"))
      (node (ref "R14") (pin "2") (pinfunction "2_2") (pintype "bidirectional"))
      (node (ref "R19") (pin "2") (pinfunction "2_2") (pintype "bidirectional"))
    )
    (net (code "70") (name "Net-(M1-PadD)") (class "Default")
      (node (ref "M1") (pin "D") (pinfunction "D_D") (pintype "passive"))
      (node (ref "M2") (pin "G") (pinfunction "G_G") (pintype "passive"))
      (node (ref "R4") (pin "1") (pinfunction "1_1") (pintype "bidirectional"))
    )
    (net (code "71") (name "Net-(M1-PadG)") (class "Default")
      (node (ref "M1") (pin "G") (pinfunction "G_G") (pintype "passive"))
      (node (ref "R28") (pin "1") (pinfunction "1_1") (pintype "bidirectional"))
      (node (ref "R36") (pin "1") (pinfunction "1_1") (pintype "bidirectional"))
    )
    (net (code "72") (name "Net-(M3-PadD)") (class "Default")
      (node (ref "M3") (pin "D") (pinfunction "D_D") (pintype "passive"))
      (node (ref "M4") (pin "G") (pinfunction "G_G") (pintype "passive"))
      (node (ref "R15") (pin "1") (pinfunction "1_1") (pintype "bidirectional"))
    )
    (net (code "73") (name "Net-(M3-PadG)") (class "Default")
      (node (ref "M3") (pin "G") (pinfunction "G_G") (pintype "passive"))
      (node (ref "R37") (pin "1") (pinfunction "1_1") (pintype "bidirectional"))
      (node (ref "R38") (pin "1") (pinfunction "1_1") (pintype "bidirectional"))
    )
    (net (code "74") (name "Net-(M5-PadD)") (class "Default")
      (node (ref "M5") (pin "D") (pinfunction "D_D") (pintype "passive"))
      (node (ref "M6") (pin "G") (pinfunction "G_G") (pintype "passive"))
      (node (ref "R26") (pin "1") (pinfunction "1_1") (pintype "bidirectional"))
    )
    (net (code "75") (name "Net-(M5-PadG)") (class "Default")
      (node (ref "M5") (pin "G") (pinfunction "G_G") (pintype "passive"))
      (node (ref "R39") (pin "1") (pinfunction "1_1") (pintype "bidirectional"))
      (node (ref "R40") (pin "1") (pinfunction "1_1") (pintype "bidirectional"))
    )
    (net (code "76") (name "Net-(Q1-PadD)") (class "Default")
      (node (ref "Q1") (pin "D") (pinfunction "D_D") (pintype "passive"))
      (node (ref "R17") (pin "2") (pinfunction "2_2") (pintype "bidirectional"))
      (node (ref "R19") (pin "1") (pinfunction "1_1") (pintype "bidirectional"))
    )
    (net (code "77") (name "Net-(Q1-PadG)") (class "Default")
      (node (ref "Q1") (pin "G") (pinfunction "G_G") (pintype "passive"))
      (node (ref "R18") (pin "1") (pinfunction "1_1") (pintype "bidirectional"))
    )
    (net (code "78") (name "Net-(Q2-PadD)") (class "Default")
      (node (ref "Q2") (pin "D") (pinfunction "D_D") (pintype "passive"))
      (node (ref "R14") (pin "1") (pinfunction "1_1") (pintype "bidirectional"))
      (node (ref "R20") (pin "2") (pinfunction "2_2") (pintype "bidirectional"))
    )
    (net (code "79") (name "Net-(Q2-PadG)") (class "Default")
      (node (ref "Q2") (pin "G") (pinfunction "G_G") (pintype "passive"))
      (node (ref "R11") (pin "1") (pinfunction "1_1") (pintype "bidirectional"))
    )
    (net (code "80") (name "Net-(R17-Pad1)") (class "Default")
      (node (ref "R17") (pin "1") (pinfunction "1_1") (pintype "bidirectional"))
      (node (ref "ST") (pin "I/O") (pinfunction "I/O_I/O") (pintype "bidirectional"))
    )
    (net (code "81") (name "Net-(R20-Pad1)") (class "Default")
      (node (ref "R20") (pin "1") (pinfunction "1_1") (pintype "bidirectional"))
      (node (ref "TH") (pin "I/O") (pinfunction "I/O_I/O") (pintype "bidirectional"))
    )
    (net (code "82") (name "Net-(U$14-Y)") (class "Default")
      (node (ref "R29") (pin "1") (pinfunction "1_1") (pintype "bidirectional"))
      (node (ref "U$14") (pin "4") (pinfunction "Y_4") (pintype "bidirectional"))
    )
    (net (code "83") (name "Net-(U$20-Y)") (class "Default")
      (node (ref "R25") (pin "1") (pinfunction "1_1") (pintype "bidirectional"))
      (node (ref "U$20") (pin "4") (pinfunction "Y_4") (pintype "bidirectional"))
    )
    (net (code "84") (name "Net-(U$23-Y)") (class "Default")
      (node (ref "R32") (pin "1") (pinfunction "1_1") (pintype "bidirectional"))
      (node (ref "U$23") (pin "4") (pinfunction "Y_4") (pintype "bidirectional"))
    )
    (net (code "85") (name "Net-(U1-BS1)") (class "Default")
      (node (ref "R22") (pin "2") (pinfunction "2_2") (pintype "bidirectional"))
      (node (ref "U1") (pin "20") (pinfunction "BS1_20") (pintype "bidirectional"))
    )
    (net (code "86") (name "Net-(U1-C1N)") (class "Default")
      (node (ref "C4") (pin "1") (pinfunction "1_1") (pintype "passive"))
      (node (ref "U1") (pin "26") (pinfunction "C1N_26") (pintype "bidirectional"))
    )
    (net (code "87") (name "Net-(U1-C1P)") (class "Default")
      (node (ref "C4") (pin "2") (pinfunction "2_2") (pintype "passive"))
      (node (ref "U1") (pin "27") (pinfunction "C1P_27") (pintype "bidirectional"))
    )
    (net (code "88") (name "Net-(U1-C2N)") (class "Default")
      (node (ref "C5") (pin "1") (pinfunction "1_1") (pintype "passive"))
      (node (ref "U1") (pin "28") (pinfunction "C2N_28") (pintype "bidirectional"))
    )
    (net (code "89") (name "Net-(U1-C2P)") (class "Default")
      (node (ref "C5") (pin "2") (pinfunction "2_2") (pintype "passive"))
      (node (ref "U1") (pin "29") (pinfunction "C2P_29") (pintype "bidirectional"))
    )
    (net (code "90") (name "Net-(U1-IREF)") (class "Default")
      (node (ref "R35") (pin "1") (pinfunction "1_1") (pintype "bidirectional"))
      (node (ref "U1") (pin "5") (pinfunction "IREF_5") (pintype "bidirectional"))
    )
    (net (code "91") (name "Net-(U1-RES#)") (class "Default")
      (node (ref "R8") (pin "2") (pinfunction "2_2") (pintype "bidirectional"))
      (node (ref "U1") (pin "17") (pinfunction "RES#_17") (pintype "bidirectional"))
    )
    (net (code "92") (name "Net-(U1-VCC)") (class "Default")
      (node (ref "C8") (pin "2") (pinfunction "2_2") (pintype "passive"))
      (node (ref "U1") (pin "3") (pinfunction "VCC_3") (pintype "bidirectional"))
    )
    (net (code "93") (name "Net-(U1-VCOMH)") (class "Default")
      (node (ref "C9") (pin "2") (pinfunction "2_2") (pintype "passive"))
      (node (ref "U1") (pin "4") (pinfunction "VCOMH_4") (pintype "bidirectional"))
    )
    (net (code "94") (name "unconnected-(IC1-ADC6-Pad19)") (class "Default")
      (node (ref "IC1") (pin "19") (pinfunction "ADC6_19") (pintype "bidirectional"))
    )
    (net (code "95") (name "unconnected-(IC1-ADC7-Pad22)") (class "Default")
      (node (ref "IC1") (pin "22") (pinfunction "ADC7_22") (pintype "bidirectional"))
    )
    (net (code "96") (name "unconnected-(IC1-PB0(ICP)-Pad12)") (class "Default")
      (node (ref "IC1") (pin "12") (pinfunction "PB0(ICP)_12") (pintype "bidirectional"))
    )
    (net (code "97") (name "unconnected-(IC1-PB1(OC1A)-Pad13)") (class "Default")
      (node (ref "IC1") (pin "13") (pinfunction "PB1(OC1A)_13") (pintype "bidirectional"))
    )
    (net (code "98") (name "unconnected-(IC1-PB2(SS{slash}OC1B)-Pad14)") (class "Default")
      (node (ref "IC1") (pin "14") (pinfunction "PB2(SS/OC1B)_14") (pintype "bidirectional"))
    )
    (net (code "99") (name "unconnected-(IC1-PC2(ADC2)-Pad25)") (class "Default")
      (node (ref "IC1") (pin "25") (pinfunction "PC2(ADC2)_25") (pintype "bidirectional"))
    )
    (net (code "100") (name "unconnected-(IC1-PD5(T1)-Pad9)") (class "Default")
      (node (ref "IC1") (pin "9") (pinfunction "PD5(T1)_9") (pintype "bidirectional"))
    )
    (net (code "101") (name "unconnected-(IC1-PD6(AIN0)-Pad10)") (class "Default")
      (node (ref "IC1") (pin "10") (pinfunction "PD6(AIN0)_10") (pintype "bidirectional"))
    )
    (net (code "102") (name "unconnected-(IC1-PD7(AIN1)-Pad11)") (class "Default")
      (node (ref "IC1") (pin "11") (pinfunction "PD7(AIN1)_11") (pintype "bidirectional"))
    )
    (net (code "103") (name "unconnected-(IC2-CE1-Pad26)") (class "Default")
      (node (ref "IC2") (pin "26") (pinfunction "CE1_26") (pintype "bidirectional"))
    )
    (net (code "104") (name "unconnected-(IC2-ID_SC-Pad28)") (class "Default")
      (node (ref "IC2") (pin "28") (pinfunction "ID_SC_28") (pintype "bidirectional"))
    )
    (net (code "105") (name "unconnected-(IC2-ID_SD-Pad27)") (class "Default")
      (node (ref "IC2") (pin "27") (pinfunction "ID_SD_27") (pintype "bidirectional"))
    )
    (net (code "106") (name "unconnected-(IC3-A2-Pad11)") (class "Default")
      (node (ref "IC3") (pin "11") (pinfunction "A2_11") (pintype "bidirectional"))
    )
    (net (code "107") (name "unconnected-(IC3-A3-Pad14)") (class "Default")
      (node (ref "IC3") (pin "14") (pinfunction "A3_14") (pintype "bidirectional"))
    )
    (net (code "108") (name "unconnected-(IC3-B2-Pad10)") (class "Default")
      (node (ref "IC3") (pin "10") (pinfunction "B2_10") (pintype "bidirectional"))
    )
    (net (code "109") (name "unconnected-(IC3-B3-Pad13)") (class "Default")
      (node (ref "IC3") (pin "13") (pinfunction "B3_13") (pintype "bidirectional"))
    )
    (net (code "110") (name "unconnected-(IC3-Y2-Pad9)") (class "Default")
      (node (ref "IC3") (pin "9") (pinfunction "Y2_9") (pintype "bidirectional"))
    )
    (net (code "111") (name "unconnected-(IC3-Y3-Pad12)") (class "Default")
      (node (ref "IC3") (pin "12") (pinfunction "Y3_12") (pintype "bidirectional"))
    )
    (net (code "112") (name "unconnected-(IC4-LED2-Pad8)") (class "Default")
      (node (ref "IC4") (pin "8") (pinfunction "LED2_8") (pintype "bidirectional"))
    )
    (net (code "113") (name "unconnected-(IC4-LED3-Pad9)") (class "Default")
      (node (ref "IC4") (pin "9") (pinfunction "LED3_9") (pintype "bidirectional"))
    )
    (net (code "114") (name "unconnected-(IC4-LED4-Pad10)") (class "Default")
      (node (ref "IC4") (pin "10") (pinfunction "LED4_10") (pintype "bidirectional"))
    )
    (net (code "115") (name "unconnected-(IC4-LED5-Pad11)") (class "Default")
      (node (ref "IC4") (pin "11") (pinfunction "LED5_11") (pintype "bidirectional"))
    )
    (net (code "116") (name "unconnected-(IC4-LED6-Pad12)") (class "Default")
      (node (ref "IC4") (pin "12") (pinfunction "LED6_12") (pintype "bidirectional"))
    )
    (net (code "117") (name "unconnected-(IC4-LED7-Pad13)") (class "Default")
      (node (ref "IC4") (pin "13") (pinfunction "LED7_13") (pintype "bidirectional"))
    )
    (net (code "118") (name "unconnected-(IC4-LED8-Pad15)") (class "Default")
      (node (ref "IC4") (pin "15") (pinfunction "LED8_15") (pintype "bidirectional"))
    )
    (net (code "119") (name "unconnected-(IC4-LED9-Pad16)") (class "Default")
      (node (ref "IC4") (pin "16") (pinfunction "LED9_16") (pintype "bidirectional"))
    )
    (net (code "120") (name "unconnected-(IC4-LED10-Pad17)") (class "Default")
      (node (ref "IC4") (pin "17") (pinfunction "LED10_17") (pintype "bidirectional"))
    )
    (net (code "121") (name "unconnected-(IC4-LED11-Pad18)") (class "Default")
      (node (ref "IC4") (pin "18") (pinfunction "LED11_18") (pintype "bidirectional"))
    )
    (net (code "122") (name "unconnected-(IC4-LED12-Pad19)") (class "Default")
      (node (ref "IC4") (pin "19") (pinfunction "LED12_19") (pintype "bidirectional"))
    )
    (net (code "123") (name "unconnected-(IC4-LED13-Pad20)") (class "Default")
      (node (ref "IC4") (pin "20") (pinfunction "LED13_20") (pintype "bidirectional"))
    )
    (net (code "124") (name "unconnected-(IC4-LED14-Pad21)") (class "Default")
      (node (ref "IC4") (pin "21") (pinfunction "LED14_21") (pintype "bidirectional"))
    )
    (net (code "125") (name "unconnected-(IC4-LED15-Pad22)") (class "Default")
      (node (ref "IC4") (pin "22") (pinfunction "LED15_22") (pintype "bidirectional"))
    )
    (net (code "126") (name "unconnected-(U1-NC-Pad1)") (class "Default")
      (node (ref "U1") (pin "1") (pinfunction "NC_1") (pintype "bidirectional"))
    )
    (net (code "127") (name "unconnected-(U1-NC-Pad24)") (class "Default")
      (node (ref "U1") (pin "24") (pinfunction "NC_24") (pintype "bidirectional"))
    )
    (net (code "128") (name "unconnected-(U1-NC-Pad30)") (class "Default")
      (node (ref "U1") (pin "30") (pinfunction "NC_30") (pintype "bidirectional"))
    )
  )
)
